# VMEConnectors.net
KiCad netlist of a schematic drawn in Altium Designer
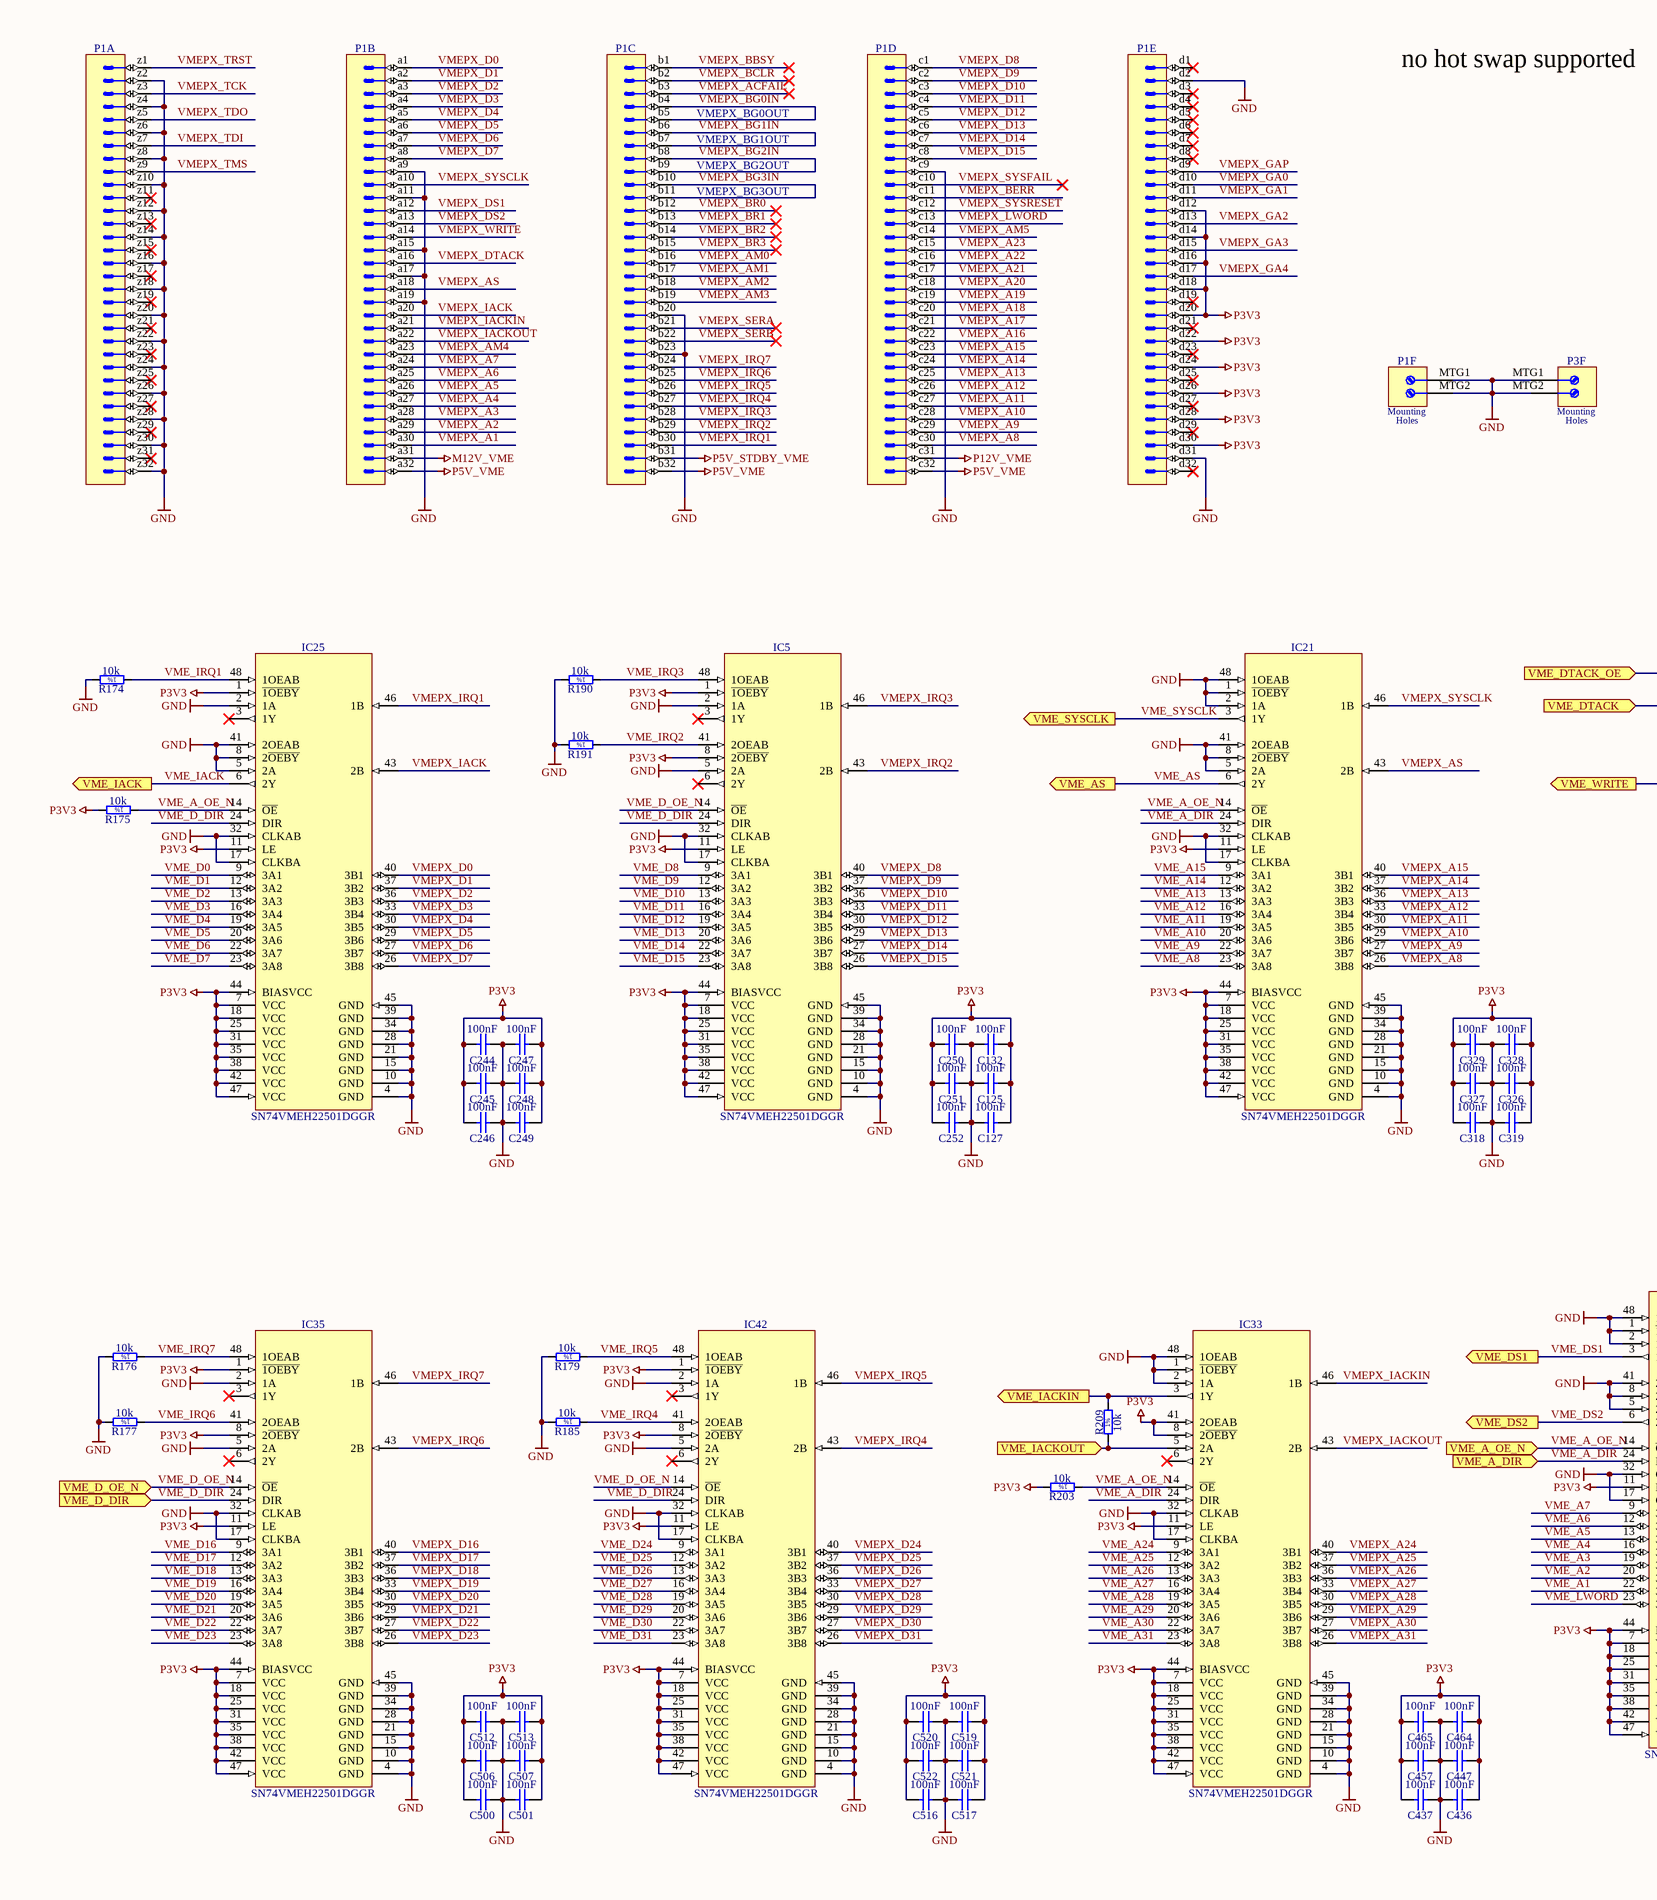
[diagram p0: VMEConnectors.SchDoc, left]
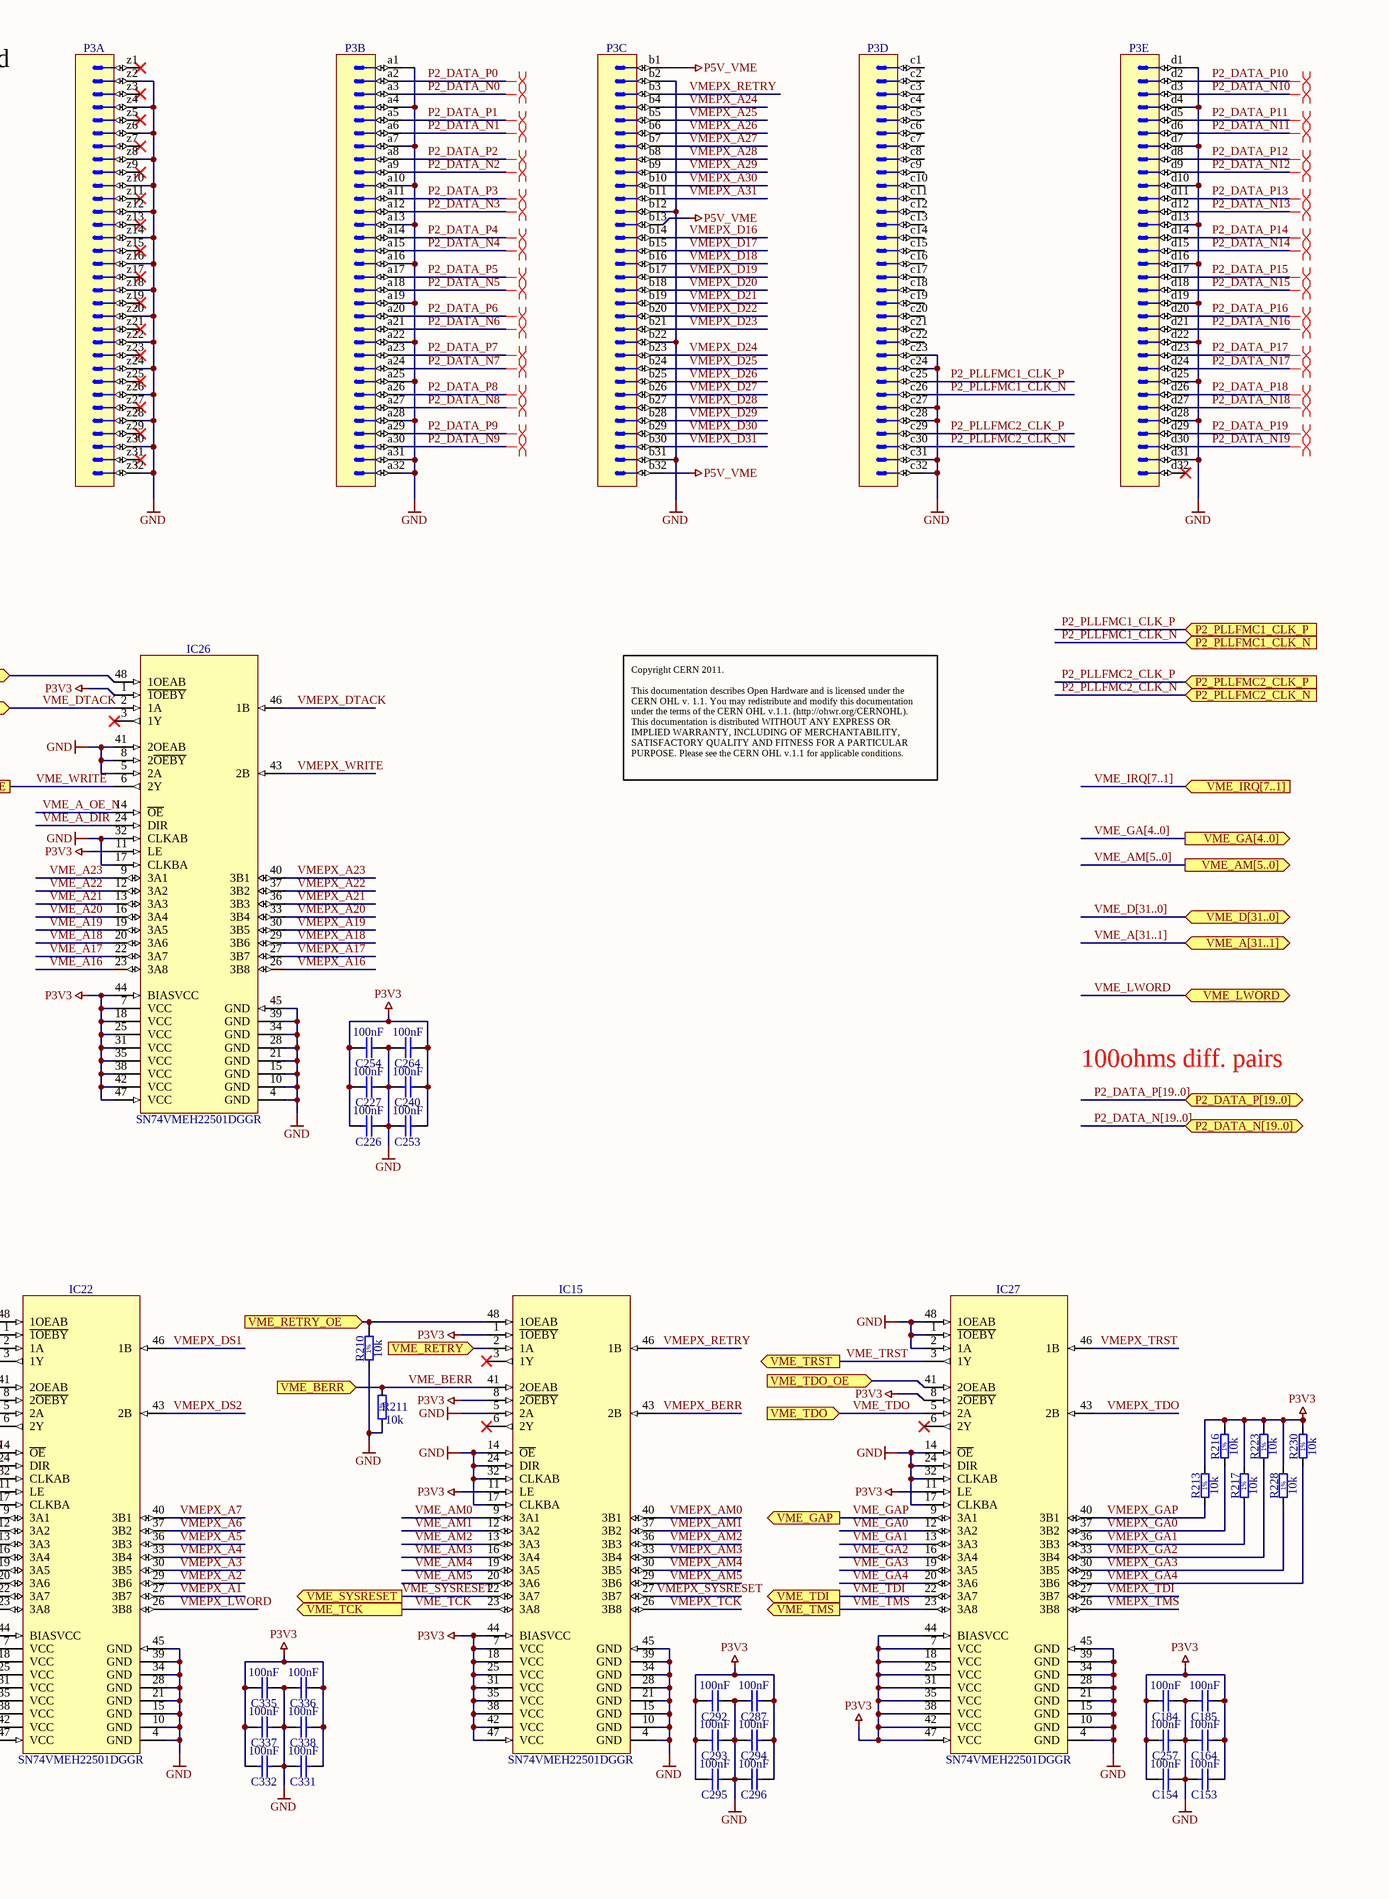
[diagram p1: VMEConnectors.SchDoc, right]

(export (version "E")
  (design (tool "Eeschema 10.0.6"))
  (components
    (comp (ref "C125")
      (value "100nF")
      (footprint "CAPC1005X55N")
      (description "Non-polarised capacitor")
      (fields
        (field (name "PART NUMBER") "CC0402_100NF_16V_10%_X7R")
        (field (name "VOLTAGE") "16V")
        (field (name "AUTHOR") "CERN DEM JLC")
      )
      (libsource (lib "Capacitors") (part "Capacitor - non polarized"))
    )
    (comp (ref "C127")
      (value "100nF")
      (footprint "CAPC1005X55N")
      (description "Non-polarised capacitor")
      (fields
        (field (name "PART NUMBER") "CC0402_100NF_16V_10%_X7R")
        (field (name "VOLTAGE") "16V")
        (field (name "AUTHOR") "CERN DEM JLC")
      )
      (libsource (lib "Capacitors") (part "Capacitor - non polarized"))
    )
    (comp (ref "C132")
      (value "100nF")
      (footprint "CAPC1005X55N")
      (description "Non-polarised capacitor")
      (fields
        (field (name "PART NUMBER") "CC0402_100NF_16V_10%_X7R")
        (field (name "VOLTAGE") "16V")
        (field (name "AUTHOR") "CERN DEM JLC")
      )
      (libsource (lib "Capacitors") (part "Capacitor - non polarized"))
    )
    (comp (ref "C153")
      (value "100nF")
      (footprint "CAPC1005X55N")
      (description "Non-polarised capacitor")
      (fields
        (field (name "PART NUMBER") "CC0402_100NF_16V_10%_X7R")
        (field (name "VOLTAGE") "16V")
        (field (name "AUTHOR") "CERN DEM JLC")
      )
      (libsource (lib "Capacitors") (part "Capacitor - non polarized"))
    )
    (comp (ref "C154")
      (value "100nF")
      (footprint "CAPC1005X55N")
      (description "Non-polarised capacitor")
      (fields
        (field (name "PART NUMBER") "CC0402_100NF_16V_10%_X7R")
        (field (name "VOLTAGE") "16V")
        (field (name "AUTHOR") "CERN DEM JLC")
      )
      (libsource (lib "Capacitors") (part "Capacitor - non polarized"))
    )
    (comp (ref "C164")
      (value "100nF")
      (footprint "CAPC1005X55N")
      (description "Non-polarised capacitor")
      (fields
        (field (name "PART NUMBER") "CC0402_100NF_16V_10%_X7R")
        (field (name "VOLTAGE") "16V")
        (field (name "AUTHOR") "CERN DEM JLC")
      )
      (libsource (lib "Capacitors") (part "Capacitor - non polarized"))
    )
    (comp (ref "C184")
      (value "100nF")
      (footprint "CAPC1005X55N")
      (description "Non-polarised capacitor")
      (fields
        (field (name "PART NUMBER") "CC0402_100NF_16V_10%_X7R")
        (field (name "VOLTAGE") "16V")
        (field (name "AUTHOR") "CERN DEM JLC")
      )
      (libsource (lib "Capacitors") (part "Capacitor - non polarized"))
    )
    (comp (ref "C185")
      (value "100nF")
      (footprint "CAPC1005X55N")
      (description "Non-polarised capacitor")
      (fields
        (field (name "PART NUMBER") "CC0402_100NF_16V_10%_X7R")
        (field (name "VOLTAGE") "16V")
        (field (name "AUTHOR") "CERN DEM JLC")
      )
      (libsource (lib "Capacitors") (part "Capacitor - non polarized"))
    )
    (comp (ref "C226")
      (value "100nF")
      (footprint "CAPC1005X55N")
      (description "Non-polarised capacitor")
      (fields
        (field (name "PART NUMBER") "CC0402_100NF_16V_10%_X7R")
        (field (name "VOLTAGE") "16V")
        (field (name "AUTHOR") "CERN DEM JLC")
      )
      (libsource (lib "Capacitors") (part "Capacitor - non polarized"))
    )
    (comp (ref "C227")
      (value "100nF")
      (footprint "CAPC1005X55N")
      (description "Non-polarised capacitor")
      (fields
        (field (name "PART NUMBER") "CC0402_100NF_16V_10%_X7R")
        (field (name "VOLTAGE") "16V")
        (field (name "AUTHOR") "CERN DEM JLC")
      )
      (libsource (lib "Capacitors") (part "Capacitor - non polarized"))
    )
    (comp (ref "C240")
      (value "100nF")
      (footprint "CAPC1005X55N")
      (description "Non-polarised capacitor")
      (fields
        (field (name "PART NUMBER") "CC0402_100NF_16V_10%_X7R")
        (field (name "VOLTAGE") "16V")
        (field (name "AUTHOR") "CERN DEM JLC")
      )
      (libsource (lib "Capacitors") (part "Capacitor - non polarized"))
    )
    (comp (ref "C244")
      (value "100nF")
      (footprint "CAPC1005X55N")
      (description "Non-polarised capacitor")
      (fields
        (field (name "PART NUMBER") "CC0402_100NF_16V_10%_X7R")
        (field (name "VOLTAGE") "16V")
        (field (name "AUTHOR") "CERN DEM JLC")
      )
      (libsource (lib "Capacitors") (part "Capacitor - non polarized"))
    )
    (comp (ref "C245")
      (value "100nF")
      (footprint "CAPC1005X55N")
      (description "Non-polarised capacitor")
      (fields
        (field (name "PART NUMBER") "CC0402_100NF_16V_10%_X7R")
        (field (name "VOLTAGE") "16V")
        (field (name "AUTHOR") "CERN DEM JLC")
      )
      (libsource (lib "Capacitors") (part "Capacitor - non polarized"))
    )
    (comp (ref "C246")
      (value "100nF")
      (footprint "CAPC1005X55N")
      (description "Non-polarised capacitor")
      (fields
        (field (name "PART NUMBER") "CC0402_100NF_16V_10%_X7R")
        (field (name "VOLTAGE") "16V")
        (field (name "AUTHOR") "CERN DEM JLC")
      )
      (libsource (lib "Capacitors") (part "Capacitor - non polarized"))
    )
    (comp (ref "C247")
      (value "100nF")
      (footprint "CAPC1005X55N")
      (description "Non-polarised capacitor")
      (fields
        (field (name "PART NUMBER") "CC0402_100NF_16V_10%_X7R")
        (field (name "VOLTAGE") "16V")
        (field (name "AUTHOR") "CERN DEM JLC")
      )
      (libsource (lib "Capacitors") (part "Capacitor - non polarized"))
    )
    (comp (ref "C248")
      (value "100nF")
      (footprint "CAPC1005X55N")
      (description "Non-polarised capacitor")
      (fields
        (field (name "PART NUMBER") "CC0402_100NF_16V_10%_X7R")
        (field (name "VOLTAGE") "16V")
        (field (name "AUTHOR") "CERN DEM JLC")
      )
      (libsource (lib "Capacitors") (part "Capacitor - non polarized"))
    )
    (comp (ref "C249")
      (value "100nF")
      (footprint "CAPC1005X55N")
      (description "Non-polarised capacitor")
      (fields
        (field (name "PART NUMBER") "CC0402_100NF_16V_10%_X7R")
        (field (name "VOLTAGE") "16V")
        (field (name "AUTHOR") "CERN DEM JLC")
      )
      (libsource (lib "Capacitors") (part "Capacitor - non polarized"))
    )
    (comp (ref "C250")
      (value "100nF")
      (footprint "CAPC1005X55N")
      (description "Non-polarised capacitor")
      (fields
        (field (name "PART NUMBER") "CC0402_100NF_16V_10%_X7R")
        (field (name "VOLTAGE") "16V")
        (field (name "AUTHOR") "CERN DEM JLC")
      )
      (libsource (lib "Capacitors") (part "Capacitor - non polarized"))
    )
    (comp (ref "C251")
      (value "100nF")
      (footprint "CAPC1005X55N")
      (description "Non-polarised capacitor")
      (fields
        (field (name "PART NUMBER") "CC0402_100NF_16V_10%_X7R")
        (field (name "VOLTAGE") "16V")
        (field (name "AUTHOR") "CERN DEM JLC")
      )
      (libsource (lib "Capacitors") (part "Capacitor - non polarized"))
    )
    (comp (ref "C252")
      (value "100nF")
      (footprint "CAPC1005X55N")
      (description "Non-polarised capacitor")
      (fields
        (field (name "PART NUMBER") "CC0402_100NF_16V_10%_X7R")
        (field (name "VOLTAGE") "16V")
        (field (name "AUTHOR") "CERN DEM JLC")
      )
      (libsource (lib "Capacitors") (part "Capacitor - non polarized"))
    )
    (comp (ref "C253")
      (value "100nF")
      (footprint "CAPC1005X55N")
      (description "Non-polarised capacitor")
      (fields
        (field (name "PART NUMBER") "CC0402_100NF_16V_10%_X7R")
        (field (name "VOLTAGE") "16V")
        (field (name "AUTHOR") "CERN DEM JLC")
      )
      (libsource (lib "Capacitors") (part "Capacitor - non polarized"))
    )
    (comp (ref "C254")
      (value "100nF")
      (footprint "CAPC1005X55N")
      (description "Non-polarised capacitor")
      (fields
        (field (name "PART NUMBER") "CC0402_100NF_16V_10%_X7R")
        (field (name "VOLTAGE") "16V")
        (field (name "AUTHOR") "CERN DEM JLC")
      )
      (libsource (lib "Capacitors") (part "Capacitor - non polarized"))
    )
    (comp (ref "C257")
      (value "100nF")
      (footprint "CAPC1005X55N")
      (description "Non-polarised capacitor")
      (fields
        (field (name "PART NUMBER") "CC0402_100NF_16V_10%_X7R")
        (field (name "VOLTAGE") "16V")
        (field (name "AUTHOR") "CERN DEM JLC")
      )
      (libsource (lib "Capacitors") (part "Capacitor - non polarized"))
    )
    (comp (ref "C264")
      (value "100nF")
      (footprint "CAPC1005X55N")
      (description "Non-polarised capacitor")
      (fields
        (field (name "PART NUMBER") "CC0402_100NF_16V_10%_X7R")
        (field (name "VOLTAGE") "16V")
        (field (name "AUTHOR") "CERN DEM JLC")
      )
      (libsource (lib "Capacitors") (part "Capacitor - non polarized"))
    )
    (comp (ref "C287")
      (value "100nF")
      (footprint "CAPC1005X55N")
      (description "Non-polarised capacitor")
      (fields
        (field (name "PART NUMBER") "CC0402_100NF_16V_10%_X7R")
        (field (name "VOLTAGE") "16V")
        (field (name "AUTHOR") "CERN DEM JLC")
      )
      (libsource (lib "Capacitors") (part "Capacitor - non polarized"))
    )
    (comp (ref "C292")
      (value "100nF")
      (footprint "CAPC1005X55N")
      (description "Non-polarised capacitor")
      (fields
        (field (name "PART NUMBER") "CC0402_100NF_16V_10%_X7R")
        (field (name "VOLTAGE") "16V")
        (field (name "AUTHOR") "CERN DEM JLC")
      )
      (libsource (lib "Capacitors") (part "Capacitor - non polarized"))
    )
    (comp (ref "C293")
      (value "100nF")
      (footprint "CAPC1005X55N")
      (description "Non-polarised capacitor")
      (fields
        (field (name "PART NUMBER") "CC0402_100NF_16V_10%_X7R")
        (field (name "VOLTAGE") "16V")
        (field (name "AUTHOR") "CERN DEM JLC")
      )
      (libsource (lib "Capacitors") (part "Capacitor - non polarized"))
    )
    (comp (ref "C294")
      (value "100nF")
      (footprint "CAPC1005X55N")
      (description "Non-polarised capacitor")
      (fields
        (field (name "PART NUMBER") "CC0402_100NF_16V_10%_X7R")
        (field (name "VOLTAGE") "16V")
        (field (name "AUTHOR") "CERN DEM JLC")
      )
      (libsource (lib "Capacitors") (part "Capacitor - non polarized"))
    )
    (comp (ref "C295")
      (value "100nF")
      (footprint "CAPC1005X55N")
      (description "Non-polarised capacitor")
      (fields
        (field (name "PART NUMBER") "CC0402_100NF_16V_10%_X7R")
        (field (name "VOLTAGE") "16V")
        (field (name "AUTHOR") "CERN DEM JLC")
      )
      (libsource (lib "Capacitors") (part "Capacitor - non polarized"))
    )
    (comp (ref "C296")
      (value "100nF")
      (footprint "CAPC1005X55N")
      (description "Non-polarised capacitor")
      (fields
        (field (name "PART NUMBER") "CC0402_100NF_16V_10%_X7R")
        (field (name "VOLTAGE") "16V")
        (field (name "AUTHOR") "CERN DEM JLC")
      )
      (libsource (lib "Capacitors") (part "Capacitor - non polarized"))
    )
    (comp (ref "C318")
      (value "100nF")
      (footprint "CAPC1005X55N")
      (description "Non-polarised capacitor")
      (fields
        (field (name "PART NUMBER") "CC0402_100NF_16V_10%_X7R")
        (field (name "VOLTAGE") "16V")
        (field (name "AUTHOR") "CERN DEM JLC")
      )
      (libsource (lib "Capacitors") (part "Capacitor - non polarized"))
    )
    (comp (ref "C319")
      (value "100nF")
      (footprint "CAPC1005X55N")
      (description "Non-polarised capacitor")
      (fields
        (field (name "PART NUMBER") "CC0402_100NF_16V_10%_X7R")
        (field (name "VOLTAGE") "16V")
        (field (name "AUTHOR") "CERN DEM JLC")
      )
      (libsource (lib "Capacitors") (part "Capacitor - non polarized"))
    )
    (comp (ref "C326")
      (value "100nF")
      (footprint "CAPC1005X55N")
      (description "Non-polarised capacitor")
      (fields
        (field (name "PART NUMBER") "CC0402_100NF_16V_10%_X7R")
        (field (name "VOLTAGE") "16V")
        (field (name "AUTHOR") "CERN DEM JLC")
      )
      (libsource (lib "Capacitors") (part "Capacitor - non polarized"))
    )
    (comp (ref "C327")
      (value "100nF")
      (footprint "CAPC1005X55N")
      (description "Non-polarised capacitor")
      (fields
        (field (name "PART NUMBER") "CC0402_100NF_16V_10%_X7R")
        (field (name "VOLTAGE") "16V")
        (field (name "AUTHOR") "CERN DEM JLC")
      )
      (libsource (lib "Capacitors") (part "Capacitor - non polarized"))
    )
    (comp (ref "C328")
      (value "100nF")
      (footprint "CAPC1005X55N")
      (description "Non-polarised capacitor")
      (fields
        (field (name "PART NUMBER") "CC0402_100NF_16V_10%_X7R")
        (field (name "VOLTAGE") "16V")
        (field (name "AUTHOR") "CERN DEM JLC")
      )
      (libsource (lib "Capacitors") (part "Capacitor - non polarized"))
    )
    (comp (ref "C329")
      (value "100nF")
      (footprint "CAPC1005X55N")
      (description "Non-polarised capacitor")
      (fields
        (field (name "PART NUMBER") "CC0402_100NF_16V_10%_X7R")
        (field (name "VOLTAGE") "16V")
        (field (name "AUTHOR") "CERN DEM JLC")
      )
      (libsource (lib "Capacitors") (part "Capacitor - non polarized"))
    )
    (comp (ref "C331")
      (value "100nF")
      (footprint "CAPC1005X55N")
      (description "Non-polarised capacitor")
      (fields
        (field (name "PART NUMBER") "CC0402_100NF_16V_10%_X7R")
        (field (name "VOLTAGE") "16V")
        (field (name "AUTHOR") "CERN DEM JLC")
      )
      (libsource (lib "Capacitors") (part "Capacitor - non polarized"))
    )
    (comp (ref "C332")
      (value "100nF")
      (footprint "CAPC1005X55N")
      (description "Non-polarised capacitor")
      (fields
        (field (name "PART NUMBER") "CC0402_100NF_16V_10%_X7R")
        (field (name "VOLTAGE") "16V")
        (field (name "AUTHOR") "CERN DEM JLC")
      )
      (libsource (lib "Capacitors") (part "Capacitor - non polarized"))
    )
    (comp (ref "C335")
      (value "100nF")
      (footprint "CAPC1005X55N")
      (description "Non-polarised capacitor")
      (fields
        (field (name "PART NUMBER") "CC0402_100NF_16V_10%_X7R")
        (field (name "VOLTAGE") "16V")
        (field (name "AUTHOR") "CERN DEM JLC")
      )
      (libsource (lib "Capacitors") (part "Capacitor - non polarized"))
    )
    (comp (ref "C336")
      (value "100nF")
      (footprint "CAPC1005X55N")
      (description "Non-polarised capacitor")
      (fields
        (field (name "PART NUMBER") "CC0402_100NF_16V_10%_X7R")
        (field (name "VOLTAGE") "16V")
        (field (name "AUTHOR") "CERN DEM JLC")
      )
      (libsource (lib "Capacitors") (part "Capacitor - non polarized"))
    )
    (comp (ref "C337")
      (value "100nF")
      (footprint "CAPC1005X55N")
      (description "Non-polarised capacitor")
      (fields
        (field (name "PART NUMBER") "CC0402_100NF_16V_10%_X7R")
        (field (name "VOLTAGE") "16V")
        (field (name "AUTHOR") "CERN DEM JLC")
      )
      (libsource (lib "Capacitors") (part "Capacitor - non polarized"))
    )
    (comp (ref "C338")
      (value "100nF")
      (footprint "CAPC1005X55N")
      (description "Non-polarised capacitor")
      (fields
        (field (name "PART NUMBER") "CC0402_100NF_16V_10%_X7R")
        (field (name "VOLTAGE") "16V")
        (field (name "AUTHOR") "CERN DEM JLC")
      )
      (libsource (lib "Capacitors") (part "Capacitor - non polarized"))
    )
    (comp (ref "C436")
      (value "100nF")
      (footprint "CAPC1005X55N")
      (description "Non-polarised capacitor")
      (fields
        (field (name "PART NUMBER") "CC0402_100NF_16V_10%_X7R")
        (field (name "VOLTAGE") "16V")
        (field (name "AUTHOR") "CERN DEM JLC")
      )
      (libsource (lib "Capacitors") (part "Capacitor - non polarized"))
    )
    (comp (ref "C437")
      (value "100nF")
      (footprint "CAPC1005X55N")
      (description "Non-polarised capacitor")
      (fields
        (field (name "PART NUMBER") "CC0402_100NF_16V_10%_X7R")
        (field (name "VOLTAGE") "16V")
        (field (name "AUTHOR") "CERN DEM JLC")
      )
      (libsource (lib "Capacitors") (part "Capacitor - non polarized"))
    )
    (comp (ref "C447")
      (value "100nF")
      (footprint "CAPC1005X55N")
      (description "Non-polarised capacitor")
      (fields
        (field (name "PART NUMBER") "CC0402_100NF_16V_10%_X7R")
        (field (name "VOLTAGE") "16V")
        (field (name "AUTHOR") "CERN DEM JLC")
      )
      (libsource (lib "Capacitors") (part "Capacitor - non polarized"))
    )
    (comp (ref "C457")
      (value "100nF")
      (footprint "CAPC1005X55N")
      (description "Non-polarised capacitor")
      (fields
        (field (name "PART NUMBER") "CC0402_100NF_16V_10%_X7R")
        (field (name "VOLTAGE") "16V")
        (field (name "AUTHOR") "CERN DEM JLC")
      )
      (libsource (lib "Capacitors") (part "Capacitor - non polarized"))
    )
    (comp (ref "C464")
      (value "100nF")
      (footprint "CAPC1005X55N")
      (description "Non-polarised capacitor")
      (fields
        (field (name "PART NUMBER") "CC0402_100NF_16V_10%_X7R")
        (field (name "VOLTAGE") "16V")
        (field (name "AUTHOR") "CERN DEM JLC")
      )
      (libsource (lib "Capacitors") (part "Capacitor - non polarized"))
    )
    (comp (ref "C465")
      (value "100nF")
      (footprint "CAPC1005X55N")
      (description "Non-polarised capacitor")
      (fields
        (field (name "PART NUMBER") "CC0402_100NF_16V_10%_X7R")
        (field (name "VOLTAGE") "16V")
        (field (name "AUTHOR") "CERN DEM JLC")
      )
      (libsource (lib "Capacitors") (part "Capacitor - non polarized"))
    )
    (comp (ref "C500")
      (value "100nF")
      (footprint "CAPC1005X55N")
      (description "Non-polarised capacitor")
      (fields
        (field (name "PART NUMBER") "CC0402_100NF_16V_10%_X7R")
        (field (name "VOLTAGE") "16V")
        (field (name "AUTHOR") "CERN DEM JLC")
      )
      (libsource (lib "Capacitors") (part "Capacitor - non polarized"))
    )
    (comp (ref "C501")
      (value "100nF")
      (footprint "CAPC1005X55N")
      (description "Non-polarised capacitor")
      (fields
        (field (name "PART NUMBER") "CC0402_100NF_16V_10%_X7R")
        (field (name "VOLTAGE") "16V")
        (field (name "AUTHOR") "CERN DEM JLC")
      )
      (libsource (lib "Capacitors") (part "Capacitor - non polarized"))
    )
    (comp (ref "C506")
      (value "100nF")
      (footprint "CAPC1005X55N")
      (description "Non-polarised capacitor")
      (fields
        (field (name "PART NUMBER") "CC0402_100NF_16V_10%_X7R")
        (field (name "VOLTAGE") "16V")
        (field (name "AUTHOR") "CERN DEM JLC")
      )
      (libsource (lib "Capacitors") (part "Capacitor - non polarized"))
    )
    (comp (ref "C507")
      (value "100nF")
      (footprint "CAPC1005X55N")
      (description "Non-polarised capacitor")
      (fields
        (field (name "PART NUMBER") "CC0402_100NF_16V_10%_X7R")
        (field (name "VOLTAGE") "16V")
        (field (name "AUTHOR") "CERN DEM JLC")
      )
      (libsource (lib "Capacitors") (part "Capacitor - non polarized"))
    )
    (comp (ref "C512")
      (value "100nF")
      (footprint "CAPC1005X55N")
      (description "Non-polarised capacitor")
      (fields
        (field (name "PART NUMBER") "CC0402_100NF_16V_10%_X7R")
        (field (name "VOLTAGE") "16V")
        (field (name "AUTHOR") "CERN DEM JLC")
      )
      (libsource (lib "Capacitors") (part "Capacitor - non polarized"))
    )
    (comp (ref "C513")
      (value "100nF")
      (footprint "CAPC1005X55N")
      (description "Non-polarised capacitor")
      (fields
        (field (name "PART NUMBER") "CC0402_100NF_16V_10%_X7R")
        (field (name "VOLTAGE") "16V")
        (field (name "AUTHOR") "CERN DEM JLC")
      )
      (libsource (lib "Capacitors") (part "Capacitor - non polarized"))
    )
    (comp (ref "C516")
      (value "100nF")
      (footprint "CAPC1005X55N")
      (description "Non-polarised capacitor")
      (fields
        (field (name "PART NUMBER") "CC0402_100NF_16V_10%_X7R")
        (field (name "VOLTAGE") "16V")
        (field (name "AUTHOR") "CERN DEM JLC")
      )
      (libsource (lib "Capacitors") (part "Capacitor - non polarized"))
    )
    (comp (ref "C517")
      (value "100nF")
      (footprint "CAPC1005X55N")
      (description "Non-polarised capacitor")
      (fields
        (field (name "PART NUMBER") "CC0402_100NF_16V_10%_X7R")
        (field (name "VOLTAGE") "16V")
        (field (name "AUTHOR") "CERN DEM JLC")
      )
      (libsource (lib "Capacitors") (part "Capacitor - non polarized"))
    )
    (comp (ref "C519")
      (value "100nF")
      (footprint "CAPC1005X55N")
      (description "Non-polarised capacitor")
      (fields
        (field (name "PART NUMBER") "CC0402_100NF_16V_10%_X7R")
        (field (name "VOLTAGE") "16V")
        (field (name "AUTHOR") "CERN DEM JLC")
      )
      (libsource (lib "Capacitors") (part "Capacitor - non polarized"))
    )
    (comp (ref "C520")
      (value "100nF")
      (footprint "CAPC1005X55N")
      (description "Non-polarised capacitor")
      (fields
        (field (name "PART NUMBER") "CC0402_100NF_16V_10%_X7R")
        (field (name "VOLTAGE") "16V")
        (field (name "AUTHOR") "CERN DEM JLC")
      )
      (libsource (lib "Capacitors") (part "Capacitor - non polarized"))
    )
    (comp (ref "C521")
      (value "100nF")
      (footprint "CAPC1005X55N")
      (description "Non-polarised capacitor")
      (fields
        (field (name "PART NUMBER") "CC0402_100NF_16V_10%_X7R")
        (field (name "VOLTAGE") "16V")
        (field (name "AUTHOR") "CERN DEM JLC")
      )
      (libsource (lib "Capacitors") (part "Capacitor - non polarized"))
    )
    (comp (ref "C522")
      (value "100nF")
      (footprint "CAPC1005X55N")
      (description "Non-polarised capacitor")
      (fields
        (field (name "PART NUMBER") "CC0402_100NF_16V_10%_X7R")
        (field (name "VOLTAGE") "16V")
        (field (name "AUTHOR") "CERN DEM JLC")
      )
      (libsource (lib "Capacitors") (part "Capacitor - non polarized"))
    )
    (comp (ref "IC5")
      (value "SN74VMEH22501DGGR")
      (footprint "SOP50P810X120-48N")
      (description "8-Bit Universal Bus Transceiver and Two 1-Bit Bus Transceivers with 3-State Outputs")
      (fields (field (name "MANUFACTURER") "TEXAS INSTRUMENTS") (field (name "AUTHOR") "CERN DEM JLC"))
      (libsource (lib "ICs And Semiconductors") (part "74VMEH22501"))
    )
    (comp (ref "IC15")
      (value "SN74VMEH22501DGGR")
      (footprint "SOP50P810X120-48N")
      (description "8-Bit Universal Bus Transceiver and Two 1-Bit Bus Transceivers with 3-State Outputs")
      (fields (field (name "MANUFACTURER") "TEXAS INSTRUMENTS") (field (name "AUTHOR") "CERN DEM JLC"))
      (libsource (lib "ICs And Semiconductors") (part "74VMEH22501"))
    )
    (comp (ref "IC21")
      (value "SN74VMEH22501DGGR")
      (footprint "SOP50P810X120-48N")
      (description "8-Bit Universal Bus Transceiver and Two 1-Bit Bus Transceivers with 3-State Outputs")
      (fields (field (name "MANUFACTURER") "TEXAS INSTRUMENTS") (field (name "AUTHOR") "CERN DEM JLC"))
      (libsource (lib "ICs And Semiconductors") (part "74VMEH22501"))
    )
    (comp (ref "IC22")
      (value "SN74VMEH22501DGGR")
      (footprint "SOP50P810X120-48N")
      (description "8-Bit Universal Bus Transceiver and Two 1-Bit Bus Transceivers with 3-State Outputs")
      (fields (field (name "MANUFACTURER") "TEXAS INSTRUMENTS") (field (name "AUTHOR") "CERN DEM JLC"))
      (libsource (lib "ICs And Semiconductors") (part "74VMEH22501"))
    )
    (comp (ref "IC25")
      (value "SN74VMEH22501DGGR")
      (footprint "SOP50P810X120-48N")
      (description "8-Bit Universal Bus Transceiver and Two 1-Bit Bus Transceivers with 3-State Outputs")
      (fields (field (name "MANUFACTURER") "TEXAS INSTRUMENTS") (field (name "AUTHOR") "CERN DEM JLC"))
      (libsource (lib "ICs And Semiconductors") (part "74VMEH22501"))
    )
    (comp (ref "IC26")
      (value "SN74VMEH22501DGGR")
      (footprint "SOP50P810X120-48N")
      (description "8-Bit Universal Bus Transceiver and Two 1-Bit Bus Transceivers with 3-State Outputs")
      (fields (field (name "MANUFACTURER") "TEXAS INSTRUMENTS") (field (name "AUTHOR") "CERN DEM JLC"))
      (libsource (lib "ICs And Semiconductors") (part "74VMEH22501"))
    )
    (comp (ref "IC27")
      (value "SN74VMEH22501DGGR")
      (footprint "SOP50P810X120-48N")
      (description "8-Bit Universal Bus Transceiver and Two 1-Bit Bus Transceivers with 3-State Outputs")
      (fields (field (name "MANUFACTURER") "TEXAS INSTRUMENTS") (field (name "AUTHOR") "CERN DEM JLC"))
      (libsource (lib "ICs And Semiconductors") (part "74VMEH22501"))
    )
    (comp (ref "IC33")
      (value "SN74VMEH22501DGGR")
      (footprint "SOP50P810X120-48N")
      (description "8-Bit Universal Bus Transceiver and Two 1-Bit Bus Transceivers with 3-State Outputs")
      (fields (field (name "MANUFACTURER") "TEXAS INSTRUMENTS") (field (name "AUTHOR") "CERN DEM JLC"))
      (libsource (lib "ICs And Semiconductors") (part "74VMEH22501"))
    )
    (comp (ref "IC35")
      (value "SN74VMEH22501DGGR")
      (footprint "SOP50P810X120-48N")
      (description "8-Bit Universal Bus Transceiver and Two 1-Bit Bus Transceivers with 3-State Outputs")
      (fields (field (name "MANUFACTURER") "TEXAS INSTRUMENTS") (field (name "AUTHOR") "CERN DEM JLC"))
      (libsource (lib "ICs And Semiconductors") (part "74VMEH22501"))
    )
    (comp (ref "IC42")
      (value "SN74VMEH22501DGGR")
      (footprint "SOP50P810X120-48N")
      (description "8-Bit Universal Bus Transceiver and Two 1-Bit Bus Transceivers with 3-State Outputs")
      (fields (field (name "MANUFACTURER") "TEXAS INSTRUMENTS") (field (name "AUTHOR") "CERN DEM JLC"))
      (libsource (lib "ICs And Semiconductors") (part "74VMEH22501"))
    )
    (comp (ref "P1")
      (value "HAR-BUS 64")
      (footprint "HARTING_02 01 160 2101")
      (description "Connector 160zabcd Male (5x32)")
      (fields
        (field (name "PART NUMBER") "HARTING_02 01 160 2101")
        (field (name "MANUFACTURER") "HARTING")
        (field (name "AUTHOR") "CERN DEM JLC")
      )
      (libsource (lib "") (part "Connector 160zabcd Male (5x32)_2"))
    )
    (comp (ref "P3")
      (value "HAR-BUS 64")
      (footprint "HARTING_02 01 160 2101")
      (description "Connector 160zabcd Male (5x32)")
      (fields
        (field (name "PART NUMBER") "HARTING_02 01 160 2101")
        (field (name "MANUFACTURER") "HARTING")
        (field (name "AUTHOR") "CERN DEM JLC")
      )
      (libsource (lib "Connectors") (part "Connector 160zabcd Male (5x32)"))
    )
    (comp (ref "R174")
      (value "10k")
      (footprint "RESC1608X55N")
      (description "Resistor - 1%")
      (fields
        (field (name "PART NUMBER") "R0603_10K_1%_0.1W_100PPM")
        (field (name "POWER") "0.1W")
        (field (name "AUTHOR") "CERN DEM JLC")
      )
      (libsource (lib "Resistors") (part "Resistor - 1%"))
    )
    (comp (ref "R175")
      (value "10k")
      (footprint "RESC1608X55N")
      (description "Resistor - 1%")
      (fields
        (field (name "PART NUMBER") "R0603_10K_1%_0.1W_100PPM")
        (field (name "POWER") "0.1W")
        (field (name "AUTHOR") "CERN DEM JLC")
      )
      (libsource (lib "Resistors") (part "Resistor - 1%"))
    )
    (comp (ref "R176")
      (value "10k")
      (footprint "RESC1608X55N")
      (description "Resistor - 1%")
      (fields
        (field (name "PART NUMBER") "R0603_10K_1%_0.1W_100PPM")
        (field (name "POWER") "0.1W")
        (field (name "AUTHOR") "CERN DEM JLC")
      )
      (libsource (lib "Resistors") (part "Resistor - 1%"))
    )
    (comp (ref "R177")
      (value "10k")
      (footprint "RESC1608X55N")
      (description "Resistor - 1%")
      (fields
        (field (name "PART NUMBER") "R0603_10K_1%_0.1W_100PPM")
        (field (name "POWER") "0.1W")
        (field (name "AUTHOR") "CERN DEM JLC")
      )
      (libsource (lib "Resistors") (part "Resistor - 1%"))
    )
    (comp (ref "R179")
      (value "10k")
      (footprint "RESC1608X55N")
      (description "Resistor - 1%")
      (fields
        (field (name "PART NUMBER") "R0603_10K_1%_0.1W_100PPM")
        (field (name "POWER") "0.1W")
        (field (name "AUTHOR") "CERN DEM JLC")
      )
      (libsource (lib "Resistors") (part "Resistor - 1%"))
    )
    (comp (ref "R185")
      (value "10k")
      (footprint "RESC1608X55N")
      (description "Resistor - 1%")
      (fields
        (field (name "PART NUMBER") "R0603_10K_1%_0.1W_100PPM")
        (field (name "POWER") "0.1W")
        (field (name "AUTHOR") "CERN DEM JLC")
      )
      (libsource (lib "Resistors") (part "Resistor - 1%"))
    )
    (comp (ref "R190")
      (value "10k")
      (footprint "RESC1608X55N")
      (description "Resistor - 1%")
      (fields
        (field (name "PART NUMBER") "R0603_10K_1%_0.1W_100PPM")
        (field (name "POWER") "0.1W")
        (field (name "AUTHOR") "CERN DEM JLC")
      )
      (libsource (lib "Resistors") (part "Resistor - 1%"))
    )
    (comp (ref "R191")
      (value "10k")
      (footprint "RESC1608X55N")
      (description "Resistor - 1%")
      (fields
        (field (name "PART NUMBER") "R0603_10K_1%_0.1W_100PPM")
        (field (name "POWER") "0.1W")
        (field (name "AUTHOR") "CERN DEM JLC")
      )
      (libsource (lib "Resistors") (part "Resistor - 1%"))
    )
    (comp (ref "R203")
      (value "10k")
      (footprint "RESC1608X55N")
      (description "Resistor - 1%")
      (fields
        (field (name "PART NUMBER") "R0603_10K_1%_0.1W_100PPM")
        (field (name "POWER") "0.1W")
        (field (name "AUTHOR") "CERN DEM JLC")
      )
      (libsource (lib "Resistors") (part "Resistor - 1%"))
    )
    (comp (ref "R209")
      (value "10k")
      (footprint "RESC1608X55N")
      (description "Resistor - 1%")
      (fields
        (field (name "PART NUMBER") "R0603_10K_1%_0.1W_100PPM")
        (field (name "POWER") "0.1W")
        (field (name "AUTHOR") "CERN DEM JLC")
      )
      (libsource (lib "Resistors") (part "Resistor - 1%"))
    )
    (comp (ref "R210")
      (value "10k")
      (footprint "RESC1608X55N")
      (description "Resistor - 1%")
      (fields
        (field (name "PART NUMBER") "R0603_10K_1%_0.1W_100PPM")
        (field (name "POWER") "0.1W")
        (field (name "AUTHOR") "CERN DEM JLC")
      )
      (libsource (lib "Resistors") (part "Resistor - 1%"))
    )
    (comp (ref "R211")
      (value "10k")
      (footprint "RESC1608X55N")
      (description "Resistor - 1%")
      (fields
        (field (name "PART NUMBER") "R0603_10K_1%_0.1W_100PPM")
        (field (name "POWER") "0.1W")
        (field (name "AUTHOR") "CERN DEM JLC")
      )
      (libsource (lib "Resistors") (part "Resistor - 1%"))
    )
    (comp (ref "R213")
      (value "10k")
      (footprint "RESC1608X55N")
      (description "Resistor - 1%")
      (fields
        (field (name "PART NUMBER") "R0603_10K_1%_0.1W_100PPM")
        (field (name "POWER") "0.1W")
        (field (name "AUTHOR") "CERN DEM JLC")
      )
      (libsource (lib "Resistors") (part "Resistor - 1%"))
    )
    (comp (ref "R216")
      (value "10k")
      (footprint "RESC1608X55N")
      (description "Resistor - 1%")
      (fields
        (field (name "PART NUMBER") "R0603_10K_1%_0.1W_100PPM")
        (field (name "POWER") "0.1W")
        (field (name "AUTHOR") "CERN DEM JLC")
      )
      (libsource (lib "Resistors") (part "Resistor - 1%"))
    )
    (comp (ref "R217")
      (value "10k")
      (footprint "RESC1608X55N")
      (description "Resistor - 1%")
      (fields
        (field (name "PART NUMBER") "R0603_10K_1%_0.1W_100PPM")
        (field (name "POWER") "0.1W")
        (field (name "AUTHOR") "CERN DEM JLC")
      )
      (libsource (lib "Resistors") (part "Resistor - 1%"))
    )
    (comp (ref "R223")
      (value "10k")
      (footprint "RESC1608X55N")
      (description "Resistor - 1%")
      (fields
        (field (name "PART NUMBER") "R0603_10K_1%_0.1W_100PPM")
        (field (name "POWER") "0.1W")
        (field (name "AUTHOR") "CERN DEM JLC")
      )
      (libsource (lib "Resistors") (part "Resistor - 1%"))
    )
    (comp (ref "R228")
      (value "10k")
      (footprint "RESC1608X55N")
      (description "Resistor - 1%")
      (fields
        (field (name "PART NUMBER") "R0603_10K_1%_0.1W_100PPM")
        (field (name "POWER") "0.1W")
        (field (name "AUTHOR") "CERN DEM JLC")
      )
      (libsource (lib "Resistors") (part "Resistor - 1%"))
    )
    (comp (ref "R230")
      (value "10k")
      (footprint "RESC1608X55N")
      (description "Resistor - 1%")
      (fields
        (field (name "PART NUMBER") "R0603_10K_1%_0.1W_100PPM")
        (field (name "POWER") "0.1W")
        (field (name "AUTHOR") "CERN DEM JLC")
      )
      (libsource (lib "Resistors") (part "Resistor - 1%"))
    )
  )
  (nets
    (net (code "1") (name "/P2_DATA_N0") (class "Default")
      (node (ref "P3") (pin "a3") (pinfunction "a3_a3") (pintype "bidirectional"))
    )
    (net (code "2") (name "/P2_DATA_N1") (class "Default")
      (node (ref "P3") (pin "a6") (pinfunction "a6_a6") (pintype "bidirectional"))
    )
    (net (code "3") (name "/P2_DATA_N2") (class "Default")
      (node (ref "P3") (pin "a9") (pinfunction "a9_a9") (pintype "bidirectional"))
    )
    (net (code "4") (name "/P2_DATA_N3") (class "Default")
      (node (ref "P3") (pin "a12") (pinfunction "a12_a12") (pintype "bidirectional"))
    )
    (net (code "5") (name "/P2_DATA_N4") (class "Default")
      (node (ref "P3") (pin "a15") (pinfunction "a15_a15") (pintype "bidirectional"))
    )
    (net (code "6") (name "/P2_DATA_N5") (class "Default")
      (node (ref "P3") (pin "a18") (pinfunction "a18_a18") (pintype "bidirectional"))
    )
    (net (code "7") (name "/P2_DATA_N6") (class "Default")
      (node (ref "P3") (pin "a21") (pinfunction "a21_a21") (pintype "bidirectional"))
    )
    (net (code "8") (name "/P2_DATA_N7") (class "Default")
      (node (ref "P3") (pin "a24") (pinfunction "a24_a24") (pintype "bidirectional"))
    )
    (net (code "9") (name "/P2_DATA_N8") (class "Default")
      (node (ref "P3") (pin "a27") (pinfunction "a27_a27") (pintype "bidirectional"))
    )
    (net (code "10") (name "/P2_DATA_N9") (class "Default")
      (node (ref "P3") (pin "a30") (pinfunction "a30_a30") (pintype "bidirectional"))
    )
    (net (code "11") (name "/P2_DATA_N10") (class "Default")
      (node (ref "P3") (pin "d3") (pinfunction "d3_d3") (pintype "bidirectional"))
    )
    (net (code "12") (name "/P2_DATA_N11") (class "Default")
      (node (ref "P3") (pin "d6") (pinfunction "d6_d6") (pintype "bidirectional"))
    )
    (net (code "13") (name "/P2_DATA_N12") (class "Default")
      (node (ref "P3") (pin "d9") (pinfunction "d9_d9") (pintype "bidirectional"))
    )
    (net (code "14") (name "/P2_DATA_N13") (class "Default")
      (node (ref "P3") (pin "d12") (pinfunction "d12_d12") (pintype "bidirectional"))
    )
    (net (code "15") (name "/P2_DATA_N14") (class "Default")
      (node (ref "P3") (pin "d15") (pinfunction "d15_d15") (pintype "bidirectional"))
    )
    (net (code "16") (name "/P2_DATA_N15") (class "Default")
      (node (ref "P3") (pin "d18") (pinfunction "d18_d18") (pintype "bidirectional"))
    )
    (net (code "17") (name "/P2_DATA_N16") (class "Default")
      (node (ref "P3") (pin "d21") (pinfunction "d21_d21") (pintype "bidirectional"))
    )
    (net (code "18") (name "/P2_DATA_N17") (class "Default")
      (node (ref "P3") (pin "d24") (pinfunction "d24_d24") (pintype "bidirectional"))
    )
    (net (code "19") (name "/P2_DATA_N18") (class "Default")
      (node (ref "P3") (pin "d27") (pinfunction "d27_d27") (pintype "bidirectional"))
    )
    (net (code "20") (name "/P2_DATA_N19") (class "Default")
      (node (ref "P3") (pin "d30") (pinfunction "d30_d30") (pintype "bidirectional"))
    )
    (net (code "22") (name "/P2_DATA_P0") (class "Default")
      (node (ref "P3") (pin "a2") (pinfunction "a2_a2") (pintype "bidirectional"))
    )
    (net (code "23") (name "/P2_DATA_P1") (class "Default")
      (node (ref "P3") (pin "a5") (pinfunction "a5_a5") (pintype "bidirectional"))
    )
    (net (code "24") (name "/P2_DATA_P2") (class "Default")
      (node (ref "P3") (pin "a8") (pinfunction "a8_a8") (pintype "bidirectional"))
    )
    (net (code "25") (name "/P2_DATA_P3") (class "Default")
      (node (ref "P3") (pin "a11") (pinfunction "a11_a11") (pintype "bidirectional"))
    )
    (net (code "26") (name "/P2_DATA_P4") (class "Default")
      (node (ref "P3") (pin "a14") (pinfunction "a14_a14") (pintype "bidirectional"))
    )
    (net (code "27") (name "/P2_DATA_P5") (class "Default")
      (node (ref "P3") (pin "a17") (pinfunction "a17_a17") (pintype "bidirectional"))
    )
    (net (code "28") (name "/P2_DATA_P6") (class "Default")
      (node (ref "P3") (pin "a20") (pinfunction "a20_a20") (pintype "bidirectional"))
    )
    (net (code "29") (name "/P2_DATA_P7") (class "Default")
      (node (ref "P3") (pin "a23") (pinfunction "a23_a23") (pintype "bidirectional"))
    )
    (net (code "30") (name "/P2_DATA_P8") (class "Default")
      (node (ref "P3") (pin "a26") (pinfunction "a26_a26") (pintype "bidirectional"))
    )
    (net (code "31") (name "/P2_DATA_P9") (class "Default")
      (node (ref "P3") (pin "a29") (pinfunction "a29_a29") (pintype "bidirectional"))
    )
    (net (code "32") (name "/P2_DATA_P10") (class "Default")
      (node (ref "P3") (pin "d2") (pinfunction "d2_d2") (pintype "bidirectional"))
    )
    (net (code "33") (name "/P2_DATA_P11") (class "Default")
      (node (ref "P3") (pin "d5") (pinfunction "d5_d5") (pintype "bidirectional"))
    )
    (net (code "34") (name "/P2_DATA_P12") (class "Default")
      (node (ref "P3") (pin "d8") (pinfunction "d8_d8") (pintype "bidirectional"))
    )
    (net (code "35") (name "/P2_DATA_P13") (class "Default")
      (node (ref "P3") (pin "d11") (pinfunction "d11_d11") (pintype "bidirectional"))
    )
    (net (code "36") (name "/P2_DATA_P14") (class "Default")
      (node (ref "P3") (pin "d14") (pinfunction "d14_d14") (pintype "bidirectional"))
    )
    (net (code "37") (name "/P2_DATA_P15") (class "Default")
      (node (ref "P3") (pin "d17") (pinfunction "d17_d17") (pintype "bidirectional"))
    )
    (net (code "38") (name "/P2_DATA_P16") (class "Default")
      (node (ref "P3") (pin "d20") (pinfunction "d20_d20") (pintype "bidirectional"))
    )
    (net (code "39") (name "/P2_DATA_P17") (class "Default")
      (node (ref "P3") (pin "d23") (pinfunction "d23_d23") (pintype "bidirectional"))
    )
    (net (code "40") (name "/P2_DATA_P18") (class "Default")
      (node (ref "P3") (pin "d26") (pinfunction "d26_d26") (pintype "bidirectional"))
    )
    (net (code "41") (name "/P2_DATA_P19") (class "Default")
      (node (ref "P3") (pin "d29") (pinfunction "d29_d29") (pintype "bidirectional"))
    )
    (net (code "43") (name "/P2_PLLFMC1_CLK_N") (class "Default")
      (node (ref "P3") (pin "c26") (pinfunction "c26_c26") (pintype "bidirectional"))
    )
    (net (code "44") (name "/P2_PLLFMC1_CLK_P") (class "Default")
      (node (ref "P3") (pin "c25") (pinfunction "c25_c25") (pintype "bidirectional"))
    )
    (net (code "45") (name "/P2_PLLFMC2_CLK_N") (class "Default")
      (node (ref "P3") (pin "c30") (pinfunction "c30_c30") (pintype "bidirectional"))
    )
    (net (code "46") (name "/P2_PLLFMC2_CLK_P") (class "Default")
      (node (ref "P3") (pin "c29") (pinfunction "c29_c29") (pintype "bidirectional"))
    )
    (net (code "47") (name "/VMEPX_A1") (class "Default")
      (node (ref "IC22") (pin "27") (pinfunction "3B7_27") (pintype "bidirectional"))
      (node (ref "P1") (pin "a30") (pinfunction "a30_a30") (pintype "bidirectional"))
    )
    (net (code "48") (name "/VMEPX_A2") (class "Default")
      (node (ref "IC22") (pin "29") (pinfunction "3B6_29") (pintype "bidirectional"))
      (node (ref "P1") (pin "a29") (pinfunction "a29_a29") (pintype "bidirectional"))
    )
    (net (code "49") (name "/VMEPX_A3") (class "Default")
      (node (ref "IC22") (pin "30") (pinfunction "3B5_30") (pintype "bidirectional"))
      (node (ref "P1") (pin "a28") (pinfunction "a28_a28") (pintype "bidirectional"))
    )
    (net (code "50") (name "/VMEPX_A4") (class "Default")
      (node (ref "IC22") (pin "33") (pinfunction "3B4_33") (pintype "bidirectional"))
      (node (ref "P1") (pin "a27") (pinfunction "a27_a27") (pintype "bidirectional"))
    )
    (net (code "51") (name "/VMEPX_A5") (class "Default")
      (node (ref "IC22") (pin "36") (pinfunction "3B3_36") (pintype "bidirectional"))
      (node (ref "P1") (pin "a26") (pinfunction "a26_a26") (pintype "bidirectional"))
    )
    (net (code "52") (name "/VMEPX_A6") (class "Default")
      (node (ref "IC22") (pin "37") (pinfunction "3B2_37") (pintype "bidirectional"))
      (node (ref "P1") (pin "a25") (pinfunction "a25_a25") (pintype "bidirectional"))
    )
    (net (code "53") (name "/VMEPX_A7") (class "Default")
      (node (ref "IC22") (pin "40") (pinfunction "3B1_40") (pintype "bidirectional"))
      (node (ref "P1") (pin "a24") (pinfunction "a24_a24") (pintype "bidirectional"))
    )
    (net (code "54") (name "/VMEPX_A8") (class "Default")
      (node (ref "IC21") (pin "26") (pinfunction "3B8_26") (pintype "bidirectional"))
      (node (ref "P1") (pin "c30") (pinfunction "c30_c30") (pintype "bidirectional"))
    )
    (net (code "55") (name "/VMEPX_A9") (class "Default")
      (node (ref "IC21") (pin "27") (pinfunction "3B7_27") (pintype "bidirectional"))
      (node (ref "P1") (pin "c29") (pinfunction "c29_c29") (pintype "bidirectional"))
    )
    (net (code "56") (name "/VMEPX_A10") (class "Default")
      (node (ref "IC21") (pin "29") (pinfunction "3B6_29") (pintype "bidirectional"))
      (node (ref "P1") (pin "c28") (pinfunction "c28_c28") (pintype "bidirectional"))
    )
    (net (code "57") (name "/VMEPX_A11") (class "Default")
      (node (ref "IC21") (pin "30") (pinfunction "3B5_30") (pintype "bidirectional"))
      (node (ref "P1") (pin "c27") (pinfunction "c27_c27") (pintype "bidirectional"))
    )
    (net (code "58") (name "/VMEPX_A12") (class "Default")
      (node (ref "IC21") (pin "33") (pinfunction "3B4_33") (pintype "bidirectional"))
      (node (ref "P1") (pin "c26") (pinfunction "c26_c26") (pintype "bidirectional"))
    )
    (net (code "59") (name "/VMEPX_A13") (class "Default")
      (node (ref "IC21") (pin "36") (pinfunction "3B3_36") (pintype "bidirectional"))
      (node (ref "P1") (pin "c25") (pinfunction "c25_c25") (pintype "bidirectional"))
    )
    (net (code "60") (name "/VMEPX_A14") (class "Default")
      (node (ref "IC21") (pin "37") (pinfunction "3B2_37") (pintype "bidirectional"))
      (node (ref "P1") (pin "c24") (pinfunction "c24_c24") (pintype "bidirectional"))
    )
    (net (code "61") (name "/VMEPX_A15") (class "Default")
      (node (ref "IC21") (pin "40") (pinfunction "3B1_40") (pintype "bidirectional"))
      (node (ref "P1") (pin "c23") (pinfunction "c23_c23") (pintype "bidirectional"))
    )
    (net (code "62") (name "/VMEPX_A16") (class "Default")
      (node (ref "IC26") (pin "26") (pinfunction "3B8_26") (pintype "bidirectional"))
      (node (ref "P1") (pin "c22") (pinfunction "c22_c22") (pintype "bidirectional"))
    )
    (net (code "63") (name "/VMEPX_A17") (class "Default")
      (node (ref "IC26") (pin "27") (pinfunction "3B7_27") (pintype "bidirectional"))
      (node (ref "P1") (pin "c21") (pinfunction "c21_c21") (pintype "bidirectional"))
    )
    (net (code "64") (name "/VMEPX_A18") (class "Default")
      (node (ref "IC26") (pin "29") (pinfunction "3B6_29") (pintype "bidirectional"))
      (node (ref "P1") (pin "c20") (pinfunction "c20_c20") (pintype "bidirectional"))
    )
    (net (code "65") (name "/VMEPX_A19") (class "Default")
      (node (ref "IC26") (pin "30") (pinfunction "3B5_30") (pintype "bidirectional"))
      (node (ref "P1") (pin "c19") (pinfunction "c19_c19") (pintype "bidirectional"))
    )
    (net (code "66") (name "/VMEPX_A20") (class "Default")
      (node (ref "IC26") (pin "33") (pinfunction "3B4_33") (pintype "bidirectional"))
      (node (ref "P1") (pin "c18") (pinfunction "c18_c18") (pintype "bidirectional"))
    )
    (net (code "67") (name "/VMEPX_A21") (class "Default")
      (node (ref "IC26") (pin "36") (pinfunction "3B3_36") (pintype "bidirectional"))
      (node (ref "P1") (pin "c17") (pinfunction "c17_c17") (pintype "bidirectional"))
    )
    (net (code "68") (name "/VMEPX_A22") (class "Default")
      (node (ref "IC26") (pin "37") (pinfunction "3B2_37") (pintype "bidirectional"))
      (node (ref "P1") (pin "c16") (pinfunction "c16_c16") (pintype "bidirectional"))
    )
    (net (code "69") (name "/VMEPX_A23") (class "Default")
      (node (ref "IC26") (pin "40") (pinfunction "3B1_40") (pintype "bidirectional"))
      (node (ref "P1") (pin "c15") (pinfunction "c15_c15") (pintype "bidirectional"))
    )
    (net (code "70") (name "/VMEPX_A24") (class "Default")
      (node (ref "IC33") (pin "40") (pinfunction "3B1_40") (pintype "bidirectional"))
      (node (ref "P3") (pin "b4") (pinfunction "b4_b4") (pintype "bidirectional"))
    )
    (net (code "71") (name "/VMEPX_A25") (class "Default")
      (node (ref "IC33") (pin "37") (pinfunction "3B2_37") (pintype "bidirectional"))
      (node (ref "P3") (pin "b5") (pinfunction "b5_b5") (pintype "bidirectional"))
    )
    (net (code "72") (name "/VMEPX_A26") (class "Default")
      (node (ref "IC33") (pin "36") (pinfunction "3B3_36") (pintype "bidirectional"))
      (node (ref "P3") (pin "b6") (pinfunction "b6_b6") (pintype "bidirectional"))
    )
    (net (code "73") (name "/VMEPX_A27") (class "Default")
      (node (ref "IC33") (pin "33") (pinfunction "3B4_33") (pintype "bidirectional"))
      (node (ref "P3") (pin "b7") (pinfunction "b7_b7") (pintype "bidirectional"))
    )
    (net (code "74") (name "/VMEPX_A28") (class "Default")
      (node (ref "IC33") (pin "30") (pinfunction "3B5_30") (pintype "bidirectional"))
      (node (ref "P3") (pin "b8") (pinfunction "b8_b8") (pintype "bidirectional"))
    )
    (net (code "75") (name "/VMEPX_A29") (class "Default")
      (node (ref "IC33") (pin "29") (pinfunction "3B6_29") (pintype "bidirectional"))
      (node (ref "P3") (pin "b9") (pinfunction "b9_b9") (pintype "bidirectional"))
    )
    (net (code "76") (name "/VMEPX_A30") (class "Default")
      (node (ref "IC33") (pin "27") (pinfunction "3B7_27") (pintype "bidirectional"))
      (node (ref "P3") (pin "b10") (pinfunction "b10_b10") (pintype "bidirectional"))
    )
    (net (code "77") (name "/VMEPX_A31") (class "Default")
      (node (ref "IC33") (pin "26") (pinfunction "3B8_26") (pintype "bidirectional"))
      (node (ref "P3") (pin "b11") (pinfunction "b11_b11") (pintype "bidirectional"))
    )
    (net (code "78") (name "/VMEPX_ACFAIL") (class "Default")
      (node (ref "P1") (pin "b3") (pinfunction "b3_b3") (pintype "bidirectional+no_connect"))
    )
    (net (code "79") (name "/VMEPX_AM0") (class "Default")
      (node (ref "IC15") (pin "40") (pinfunction "3B1_40") (pintype "bidirectional"))
      (node (ref "P1") (pin "b16") (pinfunction "b16_b16") (pintype "bidirectional"))
    )
    (net (code "80") (name "/VMEPX_AM1") (class "Default")
      (node (ref "IC15") (pin "37") (pinfunction "3B2_37") (pintype "bidirectional"))
      (node (ref "P1") (pin "b17") (pinfunction "b17_b17") (pintype "bidirectional"))
    )
    (net (code "81") (name "/VMEPX_AM2") (class "Default")
      (node (ref "IC15") (pin "36") (pinfunction "3B3_36") (pintype "bidirectional"))
      (node (ref "P1") (pin "b18") (pinfunction "b18_b18") (pintype "bidirectional"))
    )
    (net (code "82") (name "/VMEPX_AM3") (class "Default")
      (node (ref "IC15") (pin "33") (pinfunction "3B4_33") (pintype "bidirectional"))
      (node (ref "P1") (pin "b19") (pinfunction "b19_b19") (pintype "bidirectional"))
    )
    (net (code "83") (name "/VMEPX_AM4") (class "Default")
      (node (ref "IC15") (pin "30") (pinfunction "3B5_30") (pintype "bidirectional"))
      (node (ref "P1") (pin "a23") (pinfunction "a23_a23") (pintype "bidirectional"))
    )
    (net (code "84") (name "/VMEPX_AM5") (class "Default")
      (node (ref "IC15") (pin "29") (pinfunction "3B6_29") (pintype "bidirectional"))
      (node (ref "P1") (pin "c14") (pinfunction "c14_c14") (pintype "bidirectional"))
    )
    (net (code "85") (name "/VMEPX_AS") (class "Default")
      (node (ref "IC21") (pin "43") (pinfunction "2B_43") (pintype "input"))
      (node (ref "P1") (pin "a18") (pinfunction "a18_a18") (pintype "bidirectional"))
    )
    (net (code "86") (name "/VMEPX_BBSY") (class "Default")
      (node (ref "P1") (pin "b1") (pinfunction "b1_b1") (pintype "bidirectional+no_connect"))
    )
    (net (code "87") (name "/VMEPX_BCLR") (class "Default")
      (node (ref "P1") (pin "b2") (pinfunction "b2_b2") (pintype "bidirectional+no_connect"))
    )
    (net (code "88") (name "/VMEPX_BERR") (class "Default")
      (node (ref "IC15") (pin "43") (pinfunction "2B_43") (pintype "input"))
      (node (ref "P1") (pin "c11") (pinfunction "c11_c11") (pintype "bidirectional"))
    )
    (net (code "89") (name "/VMEPX_BG0IN") (class "Default")
      (node (ref "P1") (pin "b4") (pinfunction "b4_b4") (pintype "bidirectional"))
      (node (ref "P1") (pin "b5") (pinfunction "b5_b5") (pintype "bidirectional"))
    )
    (net (code "90") (name "/VMEPX_BG1IN") (class "Default")
      (node (ref "P1") (pin "b6") (pinfunction "b6_b6") (pintype "bidirectional"))
      (node (ref "P1") (pin "b7") (pinfunction "b7_b7") (pintype "bidirectional"))
    )
    (net (code "91") (name "/VMEPX_BG2IN") (class "Default")
      (node (ref "P1") (pin "b8") (pinfunction "b8_b8") (pintype "bidirectional"))
      (node (ref "P1") (pin "b9") (pinfunction "b9_b9") (pintype "bidirectional"))
    )
    (net (code "92") (name "/VMEPX_BG3IN") (class "Default")
      (node (ref "P1") (pin "b10") (pinfunction "b10_b10") (pintype "bidirectional"))
      (node (ref "P1") (pin "b11") (pinfunction "b11_b11") (pintype "bidirectional"))
    )
    (net (code "93") (name "/VMEPX_BR0") (class "Default")
      (node (ref "P1") (pin "b12") (pinfunction "b12_b12") (pintype "bidirectional+no_connect"))
    )
    (net (code "94") (name "/VMEPX_BR1") (class "Default")
      (node (ref "P1") (pin "b13") (pinfunction "b13_b13") (pintype "bidirectional+no_connect"))
    )
    (net (code "95") (name "/VMEPX_BR2") (class "Default")
      (node (ref "P1") (pin "b14") (pinfunction "b14_b14") (pintype "bidirectional+no_connect"))
    )
    (net (code "96") (name "/VMEPX_BR3") (class "Default")
      (node (ref "P1") (pin "b15") (pinfunction "b15_b15") (pintype "bidirectional+no_connect"))
    )
    (net (code "97") (name "/VMEPX_D0") (class "Default")
      (node (ref "IC25") (pin "40") (pinfunction "3B1_40") (pintype "bidirectional"))
      (node (ref "P1") (pin "a1") (pinfunction "a1_a1") (pintype "bidirectional"))
    )
    (net (code "98") (name "/VMEPX_D1") (class "Default")
      (node (ref "IC25") (pin "37") (pinfunction "3B2_37") (pintype "bidirectional"))
      (node (ref "P1") (pin "a2") (pinfunction "a2_a2") (pintype "bidirectional"))
    )
    (net (code "99") (name "/VMEPX_D2") (class "Default")
      (node (ref "IC25") (pin "36") (pinfunction "3B3_36") (pintype "bidirectional"))
      (node (ref "P1") (pin "a3") (pinfunction "a3_a3") (pintype "bidirectional"))
    )
    (net (code "100") (name "/VMEPX_D3") (class "Default")
      (node (ref "IC25") (pin "33") (pinfunction "3B4_33") (pintype "bidirectional"))
      (node (ref "P1") (pin "a4") (pinfunction "a4_a4") (pintype "bidirectional"))
    )
    (net (code "101") (name "/VMEPX_D4") (class "Default")
      (node (ref "IC25") (pin "30") (pinfunction "3B5_30") (pintype "bidirectional"))
      (node (ref "P1") (pin "a5") (pinfunction "a5_a5") (pintype "bidirectional"))
    )
    (net (code "102") (name "/VMEPX_D5") (class "Default")
      (node (ref "IC25") (pin "29") (pinfunction "3B6_29") (pintype "bidirectional"))
      (node (ref "P1") (pin "a6") (pinfunction "a6_a6") (pintype "bidirectional"))
    )
    (net (code "103") (name "/VMEPX_D6") (class "Default")
      (node (ref "IC25") (pin "27") (pinfunction "3B7_27") (pintype "bidirectional"))
      (node (ref "P1") (pin "a7") (pinfunction "a7_a7") (pintype "bidirectional"))
    )
    (net (code "104") (name "/VMEPX_D7") (class "Default")
      (node (ref "IC25") (pin "26") (pinfunction "3B8_26") (pintype "bidirectional"))
      (node (ref "P1") (pin "a8") (pinfunction "a8_a8") (pintype "bidirectional"))
    )
    (net (code "105") (name "/VMEPX_D8") (class "Default")
      (node (ref "IC5") (pin "40") (pinfunction "3B1_40") (pintype "bidirectional"))
      (node (ref "P1") (pin "c1") (pinfunction "c1_c1") (pintype "bidirectional"))
    )
    (net (code "106") (name "/VMEPX_D9") (class "Default")
      (node (ref "IC5") (pin "37") (pinfunction "3B2_37") (pintype "bidirectional"))
      (node (ref "P1") (pin "c2") (pinfunction "c2_c2") (pintype "bidirectional"))
    )
    (net (code "107") (name "/VMEPX_D10") (class "Default")
      (node (ref "IC5") (pin "36") (pinfunction "3B3_36") (pintype "bidirectional"))
      (node (ref "P1") (pin "c3") (pinfunction "c3_c3") (pintype "bidirectional"))
    )
    (net (code "108") (name "/VMEPX_D11") (class "Default")
      (node (ref "IC5") (pin "33") (pinfunction "3B4_33") (pintype "bidirectional"))
      (node (ref "P1") (pin "c4") (pinfunction "c4_c4") (pintype "bidirectional"))
    )
    (net (code "109") (name "/VMEPX_D12") (class "Default")
      (node (ref "IC5") (pin "30") (pinfunction "3B5_30") (pintype "bidirectional"))
      (node (ref "P1") (pin "c5") (pinfunction "c5_c5") (pintype "bidirectional"))
    )
    (net (code "110") (name "/VMEPX_D13") (class "Default")
      (node (ref "IC5") (pin "29") (pinfunction "3B6_29") (pintype "bidirectional"))
      (node (ref "P1") (pin "c6") (pinfunction "c6_c6") (pintype "bidirectional"))
    )
    (net (code "111") (name "/VMEPX_D14") (class "Default")
      (node (ref "IC5") (pin "27") (pinfunction "3B7_27") (pintype "bidirectional"))
      (node (ref "P1") (pin "c7") (pinfunction "c7_c7") (pintype "bidirectional"))
    )
    (net (code "112") (name "/VMEPX_D15") (class "Default")
      (node (ref "IC5") (pin "26") (pinfunction "3B8_26") (pintype "bidirectional"))
      (node (ref "P1") (pin "c8") (pinfunction "c8_c8") (pintype "bidirectional"))
    )
    (net (code "113") (name "/VMEPX_D16") (class "Default")
      (node (ref "IC35") (pin "40") (pinfunction "3B1_40") (pintype "bidirectional"))
      (node (ref "P3") (pin "b14") (pinfunction "b14_b14") (pintype "bidirectional"))
    )
    (net (code "114") (name "/VMEPX_D17") (class "Default")
      (node (ref "IC35") (pin "37") (pinfunction "3B2_37") (pintype "bidirectional"))
      (node (ref "P3") (pin "b15") (pinfunction "b15_b15") (pintype "bidirectional"))
    )
    (net (code "115") (name "/VMEPX_D18") (class "Default")
      (node (ref "IC35") (pin "36") (pinfunction "3B3_36") (pintype "bidirectional"))
      (node (ref "P3") (pin "b16") (pinfunction "b16_b16") (pintype "bidirectional"))
    )
    (net (code "116") (name "/VMEPX_D19") (class "Default")
      (node (ref "IC35") (pin "33") (pinfunction "3B4_33") (pintype "bidirectional"))
      (node (ref "P3") (pin "b17") (pinfunction "b17_b17") (pintype "bidirectional"))
    )
    (net (code "117") (name "/VMEPX_D20") (class "Default")
      (node (ref "IC35") (pin "30") (pinfunction "3B5_30") (pintype "bidirectional"))
      (node (ref "P3") (pin "b18") (pinfunction "b18_b18") (pintype "bidirectional"))
    )
    (net (code "118") (name "/VMEPX_D21") (class "Default")
      (node (ref "IC35") (pin "29") (pinfunction "3B6_29") (pintype "bidirectional"))
      (node (ref "P3") (pin "b19") (pinfunction "b19_b19") (pintype "bidirectional"))
    )
    (net (code "119") (name "/VMEPX_D22") (class "Default")
      (node (ref "IC35") (pin "27") (pinfunction "3B7_27") (pintype "bidirectional"))
      (node (ref "P3") (pin "b20") (pinfunction "b20_b20") (pintype "bidirectional"))
    )
    (net (code "120") (name "/VMEPX_D23") (class "Default")
      (node (ref "IC35") (pin "26") (pinfunction "3B8_26") (pintype "bidirectional"))
      (node (ref "P3") (pin "b21") (pinfunction "b21_b21") (pintype "bidirectional"))
    )
    (net (code "121") (name "/VMEPX_D24") (class "Default")
      (node (ref "IC42") (pin "40") (pinfunction "3B1_40") (pintype "bidirectional"))
      (node (ref "P3") (pin "b23") (pinfunction "b23_b23") (pintype "bidirectional"))
    )
    (net (code "122") (name "/VMEPX_D25") (class "Default")
      (node (ref "IC42") (pin "37") (pinfunction "3B2_37") (pintype "bidirectional"))
      (node (ref "P3") (pin "b24") (pinfunction "b24_b24") (pintype "bidirectional"))
    )
    (net (code "123") (name "/VMEPX_D26") (class "Default")
      (node (ref "IC42") (pin "36") (pinfunction "3B3_36") (pintype "bidirectional"))
      (node (ref "P3") (pin "b25") (pinfunction "b25_b25") (pintype "bidirectional"))
    )
    (net (code "124") (name "/VMEPX_D27") (class "Default")
      (node (ref "IC42") (pin "33") (pinfunction "3B4_33") (pintype "bidirectional"))
      (node (ref "P3") (pin "b26") (pinfunction "b26_b26") (pintype "bidirectional"))
    )
    (net (code "125") (name "/VMEPX_D28") (class "Default")
      (node (ref "IC42") (pin "30") (pinfunction "3B5_30") (pintype "bidirectional"))
      (node (ref "P3") (pin "b27") (pinfunction "b27_b27") (pintype "bidirectional"))
    )
    (net (code "126") (name "/VMEPX_D29") (class "Default")
      (node (ref "IC42") (pin "29") (pinfunction "3B6_29") (pintype "bidirectional"))
      (node (ref "P3") (pin "b28") (pinfunction "b28_b28") (pintype "bidirectional"))
    )
    (net (code "127") (name "/VMEPX_D30") (class "Default")
      (node (ref "IC42") (pin "27") (pinfunction "3B7_27") (pintype "bidirectional"))
      (node (ref "P3") (pin "b29") (pinfunction "b29_b29") (pintype "bidirectional"))
    )
    (net (code "128") (name "/VMEPX_D31") (class "Default")
      (node (ref "IC42") (pin "26") (pinfunction "3B8_26") (pintype "bidirectional"))
      (node (ref "P3") (pin "b30") (pinfunction "b30_b30") (pintype "bidirectional"))
    )
    (net (code "129") (name "/VMEPX_DS1") (class "Default")
      (node (ref "IC22") (pin "46") (pinfunction "1B_46") (pintype "input"))
      (node (ref "P1") (pin "a12") (pinfunction "a12_a12") (pintype "bidirectional"))
    )
    (net (code "130") (name "/VMEPX_DS2") (class "Default")
      (node (ref "IC22") (pin "43") (pinfunction "2B_43") (pintype "input"))
      (node (ref "P1") (pin "a13") (pinfunction "a13_a13") (pintype "bidirectional"))
    )
    (net (code "131") (name "/VMEPX_DTACK") (class "Default")
      (node (ref "IC26") (pin "46") (pinfunction "1B_46") (pintype "input"))
      (node (ref "P1") (pin "a16") (pinfunction "a16_a16") (pintype "bidirectional"))
    )
    (net (code "132") (name "/VMEPX_GA0") (class "Default")
      (node (ref "IC27") (pin "37") (pinfunction "3B2_37") (pintype "bidirectional"))
      (node (ref "P1") (pin "d10") (pinfunction "d10_d10") (pintype "bidirectional"))
      (node (ref "R216") (pin "1") (pinfunction "1_1") (pintype "passive"))
    )
    (net (code "133") (name "/VMEPX_GA1") (class "Default")
      (node (ref "IC27") (pin "36") (pinfunction "3B3_36") (pintype "bidirectional"))
      (node (ref "P1") (pin "d11") (pinfunction "d11_d11") (pintype "bidirectional"))
      (node (ref "R217") (pin "1") (pinfunction "1_1") (pintype "passive"))
    )
    (net (code "134") (name "/VMEPX_GA2") (class "Default")
      (node (ref "IC27") (pin "33") (pinfunction "3B4_33") (pintype "bidirectional"))
      (node (ref "P1") (pin "d13") (pinfunction "d13_d13") (pintype "bidirectional"))
      (node (ref "R223") (pin "1") (pinfunction "1_1") (pintype "passive"))
    )
    (net (code "135") (name "/VMEPX_GA3") (class "Default")
      (node (ref "IC27") (pin "30") (pinfunction "3B5_30") (pintype "bidirectional"))
      (node (ref "P1") (pin "d15") (pinfunction "d15_d15") (pintype "bidirectional"))
      (node (ref "R228") (pin "1") (pinfunction "1_1") (pintype "passive"))
    )
    (net (code "136") (name "/VMEPX_GA4") (class "Default")
      (node (ref "IC27") (pin "29") (pinfunction "3B6_29") (pintype "bidirectional"))
      (node (ref "P1") (pin "d17") (pinfunction "d17_d17") (pintype "bidirectional"))
      (node (ref "R230") (pin "1") (pinfunction "1_1") (pintype "passive"))
    )
    (net (code "137") (name "/VMEPX_GAP") (class "Default")
      (node (ref "IC27") (pin "40") (pinfunction "3B1_40") (pintype "bidirectional"))
      (node (ref "P1") (pin "d9") (pinfunction "d9_d9") (pintype "bidirectional"))
      (node (ref "R213") (pin "1") (pinfunction "1_1") (pintype "passive"))
    )
    (net (code "138") (name "/VMEPX_IACK") (class "Default")
      (node (ref "IC25") (pin "43") (pinfunction "2B_43") (pintype "input"))
      (node (ref "P1") (pin "a20") (pinfunction "a20_a20") (pintype "bidirectional"))
    )
    (net (code "139") (name "/VMEPX_IACKIN") (class "Default")
      (node (ref "IC33") (pin "46") (pinfunction "1B_46") (pintype "input"))
      (node (ref "P1") (pin "a21") (pinfunction "a21_a21") (pintype "bidirectional"))
    )
    (net (code "140") (name "/VMEPX_IACKOUT") (class "Default")
      (node (ref "IC33") (pin "43") (pinfunction "2B_43") (pintype "input"))
      (node (ref "P1") (pin "a22") (pinfunction "a22_a22") (pintype "bidirectional"))
    )
    (net (code "141") (name "/VMEPX_IRQ1") (class "Default")
      (node (ref "IC25") (pin "46") (pinfunction "1B_46") (pintype "input"))
      (node (ref "P1") (pin "b30") (pinfunction "b30_b30") (pintype "bidirectional"))
    )
    (net (code "142") (name "/VMEPX_IRQ2") (class "Default")
      (node (ref "IC5") (pin "43") (pinfunction "2B_43") (pintype "input"))
      (node (ref "P1") (pin "b29") (pinfunction "b29_b29") (pintype "bidirectional"))
    )
    (net (code "143") (name "/VMEPX_IRQ3") (class "Default")
      (node (ref "IC5") (pin "46") (pinfunction "1B_46") (pintype "input"))
      (node (ref "P1") (pin "b28") (pinfunction "b28_b28") (pintype "bidirectional"))
    )
    (net (code "144") (name "/VMEPX_IRQ4") (class "Default")
      (node (ref "IC42") (pin "43") (pinfunction "2B_43") (pintype "input"))
      (node (ref "P1") (pin "b27") (pinfunction "b27_b27") (pintype "bidirectional"))
    )
    (net (code "145") (name "/VMEPX_IRQ5") (class "Default")
      (node (ref "IC42") (pin "46") (pinfunction "1B_46") (pintype "input"))
      (node (ref "P1") (pin "b26") (pinfunction "b26_b26") (pintype "bidirectional"))
    )
    (net (code "146") (name "/VMEPX_IRQ6") (class "Default")
      (node (ref "IC35") (pin "43") (pinfunction "2B_43") (pintype "input"))
      (node (ref "P1") (pin "b25") (pinfunction "b25_b25") (pintype "bidirectional"))
    )
    (net (code "147") (name "/VMEPX_IRQ7") (class "Default")
      (node (ref "IC35") (pin "46") (pinfunction "1B_46") (pintype "input"))
      (node (ref "P1") (pin "b24") (pinfunction "b24_b24") (pintype "bidirectional"))
    )
    (net (code "148") (name "/VMEPX_LWORD") (class "Default")
      (node (ref "IC22") (pin "26") (pinfunction "3B8_26") (pintype "bidirectional"))
      (node (ref "P1") (pin "c13") (pinfunction "c13_c13") (pintype "bidirectional"))
    )
    (net (code "149") (name "/VMEPX_RETRY") (class "Default")
      (node (ref "IC15") (pin "46") (pinfunction "1B_46") (pintype "input"))
      (node (ref "P3") (pin "b3") (pinfunction "b3_b3") (pintype "bidirectional"))
    )
    (net (code "150") (name "/VMEPX_SERA") (class "Default")
      (node (ref "P1") (pin "b21") (pinfunction "b21_b21") (pintype "bidirectional+no_connect"))
    )
    (net (code "151") (name "/VMEPX_SERB") (class "Default")
      (node (ref "P1") (pin "b22") (pinfunction "b22_b22") (pintype "bidirectional+no_connect"))
    )
    (net (code "152") (name "/VMEPX_SYSCLK") (class "Default")
      (node (ref "IC21") (pin "46") (pinfunction "1B_46") (pintype "input"))
      (node (ref "P1") (pin "a10") (pinfunction "a10_a10") (pintype "bidirectional"))
    )
    (net (code "153") (name "/VMEPX_SYSFAIL") (class "Default")
      (node (ref "P1") (pin "c10") (pinfunction "c10_c10") (pintype "bidirectional+no_connect"))
    )
    (net (code "154") (name "/VMEPX_SYSRESET") (class "Default")
      (node (ref "IC15") (pin "27") (pinfunction "3B7_27") (pintype "bidirectional"))
      (node (ref "P1") (pin "c12") (pinfunction "c12_c12") (pintype "bidirectional"))
    )
    (net (code "155") (name "/VMEPX_TCK") (class "Default")
      (node (ref "IC15") (pin "26") (pinfunction "3B8_26") (pintype "bidirectional"))
      (node (ref "P1") (pin "z3") (pinfunction "z3_z3") (pintype "bidirectional"))
    )
    (net (code "156") (name "/VMEPX_TDI") (class "Default")
      (node (ref "IC27") (pin "27") (pinfunction "3B7_27") (pintype "bidirectional"))
      (node (ref "P1") (pin "z7") (pinfunction "z7_z7") (pintype "bidirectional"))
    )
    (net (code "157") (name "/VMEPX_TDO") (class "Default")
      (node (ref "IC27") (pin "43") (pinfunction "2B_43") (pintype "input"))
      (node (ref "P1") (pin "z5") (pinfunction "z5_z5") (pintype "bidirectional"))
    )
    (net (code "158") (name "/VMEPX_TMS") (class "Default")
      (node (ref "IC27") (pin "26") (pinfunction "3B8_26") (pintype "bidirectional"))
      (node (ref "P1") (pin "z9") (pinfunction "z9_z9") (pintype "bidirectional"))
    )
    (net (code "159") (name "/VMEPX_TRST") (class "Default")
      (node (ref "IC27") (pin "46") (pinfunction "1B_46") (pintype "input"))
      (node (ref "P1") (pin "z1") (pinfunction "z1_z1") (pintype "bidirectional"))
    )
    (net (code "160") (name "/VMEPX_WRITE") (class "Default")
      (node (ref "IC26") (pin "43") (pinfunction "2B_43") (pintype "input"))
      (node (ref "P1") (pin "a14") (pinfunction "a14_a14") (pintype "bidirectional"))
    )
    (net (code "161") (name "/VME_A1") (class "Default")
      (node (ref "IC22") (pin "22") (pinfunction "3A7_22") (pintype "bidirectional"))
    )
    (net (code "162") (name "/VME_A2") (class "Default")
      (node (ref "IC22") (pin "20") (pinfunction "3A6_20") (pintype "bidirectional"))
    )
    (net (code "163") (name "/VME_A3") (class "Default")
      (node (ref "IC22") (pin "19") (pinfunction "3A5_19") (pintype "bidirectional"))
    )
    (net (code "164") (name "/VME_A4") (class "Default")
      (node (ref "IC22") (pin "16") (pinfunction "3A4_16") (pintype "bidirectional"))
    )
    (net (code "165") (name "/VME_A5") (class "Default")
      (node (ref "IC22") (pin "13") (pinfunction "3A3_13") (pintype "bidirectional"))
    )
    (net (code "166") (name "/VME_A6") (class "Default")
      (node (ref "IC22") (pin "12") (pinfunction "3A2_12") (pintype "bidirectional"))
    )
    (net (code "167") (name "/VME_A7") (class "Default")
      (node (ref "IC22") (pin "9") (pinfunction "3A1_9") (pintype "bidirectional"))
    )
    (net (code "168") (name "/VME_A8") (class "Default")
      (node (ref "IC21") (pin "23") (pinfunction "3A8_23") (pintype "bidirectional"))
    )
    (net (code "169") (name "/VME_A9") (class "Default")
      (node (ref "IC21") (pin "22") (pinfunction "3A7_22") (pintype "bidirectional"))
    )
    (net (code "170") (name "/VME_A10") (class "Default")
      (node (ref "IC21") (pin "20") (pinfunction "3A6_20") (pintype "bidirectional"))
    )
    (net (code "171") (name "/VME_A11") (class "Default")
      (node (ref "IC21") (pin "19") (pinfunction "3A5_19") (pintype "bidirectional"))
    )
    (net (code "172") (name "/VME_A12") (class "Default")
      (node (ref "IC21") (pin "16") (pinfunction "3A4_16") (pintype "bidirectional"))
    )
    (net (code "173") (name "/VME_A13") (class "Default")
      (node (ref "IC21") (pin "13") (pinfunction "3A3_13") (pintype "bidirectional"))
    )
    (net (code "174") (name "/VME_A14") (class "Default")
      (node (ref "IC21") (pin "12") (pinfunction "3A2_12") (pintype "bidirectional"))
    )
    (net (code "175") (name "/VME_A15") (class "Default")
      (node (ref "IC21") (pin "9") (pinfunction "3A1_9") (pintype "bidirectional"))
    )
    (net (code "176") (name "/VME_A16") (class "Default")
      (node (ref "IC26") (pin "23") (pinfunction "3A8_23") (pintype "bidirectional"))
    )
    (net (code "177") (name "/VME_A17") (class "Default")
      (node (ref "IC26") (pin "22") (pinfunction "3A7_22") (pintype "bidirectional"))
    )
    (net (code "178") (name "/VME_A18") (class "Default")
      (node (ref "IC26") (pin "20") (pinfunction "3A6_20") (pintype "bidirectional"))
    )
    (net (code "179") (name "/VME_A19") (class "Default")
      (node (ref "IC26") (pin "19") (pinfunction "3A5_19") (pintype "bidirectional"))
    )
    (net (code "180") (name "/VME_A20") (class "Default")
      (node (ref "IC26") (pin "16") (pinfunction "3A4_16") (pintype "bidirectional"))
    )
    (net (code "181") (name "/VME_A21") (class "Default")
      (node (ref "IC26") (pin "13") (pinfunction "3A3_13") (pintype "bidirectional"))
    )
    (net (code "182") (name "/VME_A22") (class "Default")
      (node (ref "IC26") (pin "12") (pinfunction "3A2_12") (pintype "bidirectional"))
    )
    (net (code "183") (name "/VME_A23") (class "Default")
      (node (ref "IC26") (pin "9") (pinfunction "3A1_9") (pintype "bidirectional"))
    )
    (net (code "184") (name "/VME_A24") (class "Default")
      (node (ref "IC33") (pin "9") (pinfunction "3A1_9") (pintype "bidirectional"))
    )
    (net (code "185") (name "/VME_A25") (class "Default")
      (node (ref "IC33") (pin "12") (pinfunction "3A2_12") (pintype "bidirectional"))
    )
    (net (code "186") (name "/VME_A26") (class "Default")
      (node (ref "IC33") (pin "13") (pinfunction "3A3_13") (pintype "bidirectional"))
    )
    (net (code "187") (name "/VME_A27") (class "Default")
      (node (ref "IC33") (pin "16") (pinfunction "3A4_16") (pintype "bidirectional"))
    )
    (net (code "188") (name "/VME_A28") (class "Default")
      (node (ref "IC33") (pin "19") (pinfunction "3A5_19") (pintype "bidirectional"))
    )
    (net (code "189") (name "/VME_A29") (class "Default")
      (node (ref "IC33") (pin "20") (pinfunction "3A6_20") (pintype "bidirectional"))
    )
    (net (code "190") (name "/VME_A30") (class "Default")
      (node (ref "IC33") (pin "22") (pinfunction "3A7_22") (pintype "bidirectional"))
    )
    (net (code "191") (name "/VME_A31") (class "Default")
      (node (ref "IC33") (pin "23") (pinfunction "3A8_23") (pintype "bidirectional"))
    )
    (net (code "192") (name "/VME_AM0") (class "Default")
      (node (ref "IC15") (pin "9") (pinfunction "3A1_9") (pintype "bidirectional"))
    )
    (net (code "193") (name "/VME_AM1") (class "Default")
      (node (ref "IC15") (pin "12") (pinfunction "3A2_12") (pintype "bidirectional"))
    )
    (net (code "194") (name "/VME_AM2") (class "Default")
      (node (ref "IC15") (pin "13") (pinfunction "3A3_13") (pintype "bidirectional"))
    )
    (net (code "195") (name "/VME_AM3") (class "Default")
      (node (ref "IC15") (pin "16") (pinfunction "3A4_16") (pintype "bidirectional"))
    )
    (net (code "196") (name "/VME_AM4") (class "Default")
      (node (ref "IC15") (pin "19") (pinfunction "3A5_19") (pintype "bidirectional"))
    )
    (net (code "197") (name "/VME_AM5") (class "Default")
      (node (ref "IC15") (pin "20") (pinfunction "3A6_20") (pintype "bidirectional"))
    )
    (net (code "199") (name "/VME_AS") (class "Default")
      (node (ref "IC21") (pin "6") (pinfunction "2Y_6") (pintype "output"))
    )
    (net (code "201") (name "/VME_A_DIR") (class "Default")
      (node (ref "IC21") (pin "24") (pinfunction "DIR_24") (pintype "input"))
      (node (ref "IC22") (pin "24") (pinfunction "DIR_24") (pintype "input"))
      (node (ref "IC26") (pin "24") (pinfunction "DIR_24") (pintype "input"))
      (node (ref "IC33") (pin "24") (pinfunction "DIR_24") (pintype "input"))
    )
    (net (code "202") (name "/VME_A_OE_N") (class "Default")
      (node (ref "IC21") (pin "14") (pinfunction "~{OE}_14") (pintype "input"))
      (node (ref "IC22") (pin "14") (pinfunction "~{OE}_14") (pintype "input"))
      (node (ref "IC25") (pin "14") (pinfunction "~{OE}_14") (pintype "input"))
      (node (ref "IC26") (pin "14") (pinfunction "~{OE}_14") (pintype "input"))
      (node (ref "IC33") (pin "14") (pinfunction "~{OE}_14") (pintype "input"))
      (node (ref "R175") (pin "1") (pinfunction "1_1") (pintype "passive"))
      (node (ref "R203") (pin "1") (pinfunction "1_1") (pintype "passive"))
    )
    (net (code "203") (name "/VME_BERR") (class "Default")
      (node (ref "IC15") (pin "41") (pinfunction "2OEAB_41") (pintype "input"))
      (node (ref "R211") (pin "2") (pinfunction "2_2") (pintype "passive"))
    )
    (net (code "204") (name "/VME_D0") (class "Default")
      (node (ref "IC25") (pin "9") (pinfunction "3A1_9") (pintype "bidirectional"))
    )
    (net (code "205") (name "/VME_D1") (class "Default")
      (node (ref "IC25") (pin "12") (pinfunction "3A2_12") (pintype "bidirectional"))
    )
    (net (code "206") (name "/VME_D2") (class "Default")
      (node (ref "IC25") (pin "13") (pinfunction "3A3_13") (pintype "bidirectional"))
    )
    (net (code "207") (name "/VME_D3") (class "Default")
      (node (ref "IC25") (pin "16") (pinfunction "3A4_16") (pintype "bidirectional"))
    )
    (net (code "208") (name "/VME_D4") (class "Default")
      (node (ref "IC25") (pin "19") (pinfunction "3A5_19") (pintype "bidirectional"))
    )
    (net (code "209") (name "/VME_D5") (class "Default")
      (node (ref "IC25") (pin "20") (pinfunction "3A6_20") (pintype "bidirectional"))
    )
    (net (code "210") (name "/VME_D6") (class "Default")
      (node (ref "IC25") (pin "22") (pinfunction "3A7_22") (pintype "bidirectional"))
    )
    (net (code "211") (name "/VME_D7") (class "Default")
      (node (ref "IC25") (pin "23") (pinfunction "3A8_23") (pintype "bidirectional"))
    )
    (net (code "212") (name "/VME_D8") (class "Default")
      (node (ref "IC5") (pin "9") (pinfunction "3A1_9") (pintype "bidirectional"))
    )
    (net (code "213") (name "/VME_D9") (class "Default")
      (node (ref "IC5") (pin "12") (pinfunction "3A2_12") (pintype "bidirectional"))
    )
    (net (code "214") (name "/VME_D10") (class "Default")
      (node (ref "IC5") (pin "13") (pinfunction "3A3_13") (pintype "bidirectional"))
    )
    (net (code "215") (name "/VME_D11") (class "Default")
      (node (ref "IC5") (pin "16") (pinfunction "3A4_16") (pintype "bidirectional"))
    )
    (net (code "216") (name "/VME_D12") (class "Default")
      (node (ref "IC5") (pin "19") (pinfunction "3A5_19") (pintype "bidirectional"))
    )
    (net (code "217") (name "/VME_D13") (class "Default")
      (node (ref "IC5") (pin "20") (pinfunction "3A6_20") (pintype "bidirectional"))
    )
    (net (code "218") (name "/VME_D14") (class "Default")
      (node (ref "IC5") (pin "22") (pinfunction "3A7_22") (pintype "bidirectional"))
    )
    (net (code "219") (name "/VME_D15") (class "Default")
      (node (ref "IC5") (pin "23") (pinfunction "3A8_23") (pintype "bidirectional"))
    )
    (net (code "220") (name "/VME_D16") (class "Default")
      (node (ref "IC35") (pin "9") (pinfunction "3A1_9") (pintype "bidirectional"))
    )
    (net (code "221") (name "/VME_D17") (class "Default")
      (node (ref "IC35") (pin "12") (pinfunction "3A2_12") (pintype "bidirectional"))
    )
    (net (code "222") (name "/VME_D18") (class "Default")
      (node (ref "IC35") (pin "13") (pinfunction "3A3_13") (pintype "bidirectional"))
    )
    (net (code "223") (name "/VME_D19") (class "Default")
      (node (ref "IC35") (pin "16") (pinfunction "3A4_16") (pintype "bidirectional"))
    )
    (net (code "224") (name "/VME_D20") (class "Default")
      (node (ref "IC35") (pin "19") (pinfunction "3A5_19") (pintype "bidirectional"))
    )
    (net (code "225") (name "/VME_D21") (class "Default")
      (node (ref "IC35") (pin "20") (pinfunction "3A6_20") (pintype "bidirectional"))
    )
    (net (code "226") (name "/VME_D22") (class "Default")
      (node (ref "IC35") (pin "22") (pinfunction "3A7_22") (pintype "bidirectional"))
    )
    (net (code "227") (name "/VME_D23") (class "Default")
      (node (ref "IC35") (pin "23") (pinfunction "3A8_23") (pintype "bidirectional"))
    )
    (net (code "228") (name "/VME_D24") (class "Default")
      (node (ref "IC42") (pin "9") (pinfunction "3A1_9") (pintype "bidirectional"))
    )
    (net (code "229") (name "/VME_D25") (class "Default")
      (node (ref "IC42") (pin "12") (pinfunction "3A2_12") (pintype "bidirectional"))
    )
    (net (code "230") (name "/VME_D26") (class "Default")
      (node (ref "IC42") (pin "13") (pinfunction "3A3_13") (pintype "bidirectional"))
    )
    (net (code "231") (name "/VME_D27") (class "Default")
      (node (ref "IC42") (pin "16") (pinfunction "3A4_16") (pintype "bidirectional"))
    )
    (net (code "232") (name "/VME_D28") (class "Default")
      (node (ref "IC42") (pin "19") (pinfunction "3A5_19") (pintype "bidirectional"))
    )
    (net (code "233") (name "/VME_D29") (class "Default")
      (node (ref "IC42") (pin "20") (pinfunction "3A6_20") (pintype "bidirectional"))
    )
    (net (code "234") (name "/VME_D30") (class "Default")
      (node (ref "IC42") (pin "22") (pinfunction "3A7_22") (pintype "bidirectional"))
    )
    (net (code "235") (name "/VME_D31") (class "Default")
      (node (ref "IC42") (pin "23") (pinfunction "3A8_23") (pintype "bidirectional"))
    )
    (net (code "236") (name "/VME_DS1") (class "Default")
      (node (ref "IC22") (pin "3") (pinfunction "1Y_3") (pintype "output"))
    )
    (net (code "237") (name "/VME_DS2") (class "Default")
      (node (ref "IC22") (pin "6") (pinfunction "2Y_6") (pintype "output"))
    )
    (net (code "238") (name "/VME_DTACK") (class "Default")
      (node (ref "IC26") (pin "2") (pinfunction "1A_2") (pintype "input"))
    )
    (net (code "239") (name "/VME_DTACK_OE") (class "Default")
      (node (ref "IC26") (pin "48") (pinfunction "1OEAB_48") (pintype "input"))
    )
    (net (code "241") (name "/VME_D_DIR") (class "Default")
      (node (ref "IC25") (pin "24") (pinfunction "DIR_24") (pintype "input"))
      (node (ref "IC35") (pin "24") (pinfunction "DIR_24") (pintype "input"))
      (node (ref "IC42") (pin "24") (pinfunction "DIR_24") (pintype "input"))
      (node (ref "IC5") (pin "24") (pinfunction "DIR_24") (pintype "input"))
    )
    (net (code "242") (name "/VME_D_OE_N") (class "Default")
      (node (ref "IC35") (pin "14") (pinfunction "~{OE}_14") (pintype "input"))
      (node (ref "IC42") (pin "14") (pinfunction "~{OE}_14") (pintype "input"))
      (node (ref "IC5") (pin "14") (pinfunction "~{OE}_14") (pintype "input"))
    )
    (net (code "243") (name "/VME_GA0") (class "Default")
      (node (ref "IC27") (pin "12") (pinfunction "3A2_12") (pintype "bidirectional"))
    )
    (net (code "244") (name "/VME_GA1") (class "Default")
      (node (ref "IC27") (pin "13") (pinfunction "3A3_13") (pintype "bidirectional"))
    )
    (net (code "245") (name "/VME_GA2") (class "Default")
      (node (ref "IC27") (pin "16") (pinfunction "3A4_16") (pintype "bidirectional"))
    )
    (net (code "246") (name "/VME_GA3") (class "Default")
      (node (ref "IC27") (pin "19") (pinfunction "3A5_19") (pintype "bidirectional"))
    )
    (net (code "247") (name "/VME_GA4") (class "Default")
      (node (ref "IC27") (pin "20") (pinfunction "3A6_20") (pintype "bidirectional"))
    )
    (net (code "248") (name "/VME_GAP") (class "Default")
      (node (ref "IC27") (pin "9") (pinfunction "3A1_9") (pintype "bidirectional"))
    )
    (net (code "250") (name "/VME_IACK") (class "Default")
      (node (ref "IC25") (pin "6") (pinfunction "2Y_6") (pintype "output"))
    )
    (net (code "251") (name "/VME_IACKIN") (class "Default")
      (node (ref "IC33") (pin "3") (pinfunction "1Y_3") (pintype "output"))
      (node (ref "R209") (pin "2") (pinfunction "2_2") (pintype "passive"))
    )
    (net (code "252") (name "/VME_IACKOUT") (class "Default")
      (node (ref "IC33") (pin "5") (pinfunction "2A_5") (pintype "input"))
      (node (ref "R209") (pin "1") (pinfunction "1_1") (pintype "passive"))
    )
    (net (code "253") (name "/VME_IRQ1") (class "Default")
      (node (ref "IC25") (pin "48") (pinfunction "1OEAB_48") (pintype "input"))
      (node (ref "R174") (pin "1") (pinfunction "1_1") (pintype "passive"))
    )
    (net (code "254") (name "/VME_IRQ2") (class "Default")
      (node (ref "IC5") (pin "41") (pinfunction "2OEAB_41") (pintype "input"))
      (node (ref "R191") (pin "1") (pinfunction "1_1") (pintype "passive"))
    )
    (net (code "255") (name "/VME_IRQ3") (class "Default")
      (node (ref "IC5") (pin "48") (pinfunction "1OEAB_48") (pintype "input"))
      (node (ref "R190") (pin "1") (pinfunction "1_1") (pintype "passive"))
    )
    (net (code "256") (name "/VME_IRQ4") (class "Default")
      (node (ref "IC42") (pin "41") (pinfunction "2OEAB_41") (pintype "input"))
      (node (ref "R185") (pin "1") (pinfunction "1_1") (pintype "passive"))
    )
    (net (code "257") (name "/VME_IRQ5") (class "Default")
      (node (ref "IC42") (pin "48") (pinfunction "1OEAB_48") (pintype "input"))
      (node (ref "R179") (pin "1") (pinfunction "1_1") (pintype "passive"))
    )
    (net (code "258") (name "/VME_IRQ6") (class "Default")
      (node (ref "IC35") (pin "41") (pinfunction "2OEAB_41") (pintype "input"))
      (node (ref "R177") (pin "1") (pinfunction "1_1") (pintype "passive"))
    )
    (net (code "259") (name "/VME_IRQ7") (class "Default")
      (node (ref "IC35") (pin "48") (pinfunction "1OEAB_48") (pintype "input"))
      (node (ref "R176") (pin "1") (pinfunction "1_1") (pintype "passive"))
    )
    (net (code "261") (name "/VME_LWORD") (class "Default")
      (node (ref "IC22") (pin "23") (pinfunction "3A8_23") (pintype "bidirectional"))
    )
    (net (code "262") (name "/VME_RETRY") (class "Default")
      (node (ref "IC15") (pin "2") (pinfunction "1A_2") (pintype "input"))
    )
    (net (code "263") (name "/VME_RETRY_OE") (class "Default")
      (node (ref "IC15") (pin "48") (pinfunction "1OEAB_48") (pintype "input"))
      (node (ref "R210") (pin "2") (pinfunction "2_2") (pintype "passive"))
    )
    (net (code "264") (name "/VME_SYSCLK") (class "Default")
      (node (ref "IC21") (pin "3") (pinfunction "1Y_3") (pintype "output"))
    )
    (net (code "265") (name "/VME_SYSRESET") (class "Default")
      (node (ref "IC15") (pin "22") (pinfunction "3A7_22") (pintype "bidirectional"))
    )
    (net (code "266") (name "/VME_TCK") (class "Default")
      (node (ref "IC15") (pin "23") (pinfunction "3A8_23") (pintype "bidirectional"))
    )
    (net (code "267") (name "/VME_TDI") (class "Default")
      (node (ref "IC27") (pin "22") (pinfunction "3A7_22") (pintype "bidirectional"))
    )
    (net (code "268") (name "/VME_TDO") (class "Default")
      (node (ref "IC27") (pin "5") (pinfunction "2A_5") (pintype "input"))
    )
    (net (code "269") (name "/VME_TDO_OE") (class "Default")
      (node (ref "IC27") (pin "41") (pinfunction "2OEAB_41") (pintype "input"))
    )
    (net (code "270") (name "/VME_TMS") (class "Default")
      (node (ref "IC27") (pin "23") (pinfunction "3A8_23") (pintype "bidirectional"))
    )
    (net (code "271") (name "/VME_TRST") (class "Default")
      (node (ref "IC27") (pin "3") (pinfunction "1Y_3") (pintype "output"))
    )
    (net (code "272") (name "/VME_WRITE") (class "Default")
      (node (ref "IC26") (pin "6") (pinfunction "2Y_6") (pintype "output"))
    )
    (net (code "273") (name "GND") (class "Default")
      (node (ref "C125") (pin "2") (pinfunction "2_2") (pintype "passive"))
      (node (ref "C127") (pin "2") (pinfunction "2_2") (pintype "passive"))
      (node (ref "C132") (pin "2") (pinfunction "2_2") (pintype "passive"))
      (node (ref "C153") (pin "2") (pinfunction "2_2") (pintype "passive"))
      (node (ref "C154") (pin "1") (pinfunction "1_1") (pintype "passive"))
      (node (ref "C164") (pin "2") (pinfunction "2_2") (pintype "passive"))
      (node (ref "C184") (pin "1") (pinfunction "1_1") (pintype "passive"))
      (node (ref "C185") (pin "2") (pinfunction "2_2") (pintype "passive"))
      (node (ref "C226") (pin "1") (pinfunction "1_1") (pintype "passive"))
      (node (ref "C227") (pin "1") (pinfunction "1_1") (pintype "passive"))
      (node (ref "C240") (pin "2") (pinfunction "2_2") (pintype "passive"))
      (node (ref "C244") (pin "1") (pinfunction "1_1") (pintype "passive"))
      (node (ref "C245") (pin "1") (pinfunction "1_1") (pintype "passive"))
      (node (ref "C246") (pin "1") (pinfunction "1_1") (pintype "passive"))
      (node (ref "C247") (pin "2") (pinfunction "2_2") (pintype "passive"))
      (node (ref "C248") (pin "2") (pinfunction "2_2") (pintype "passive"))
      (node (ref "C249") (pin "2") (pinfunction "2_2") (pintype "passive"))
      (node (ref "C250") (pin "1") (pinfunction "1_1") (pintype "passive"))
      (node (ref "C251") (pin "1") (pinfunction "1_1") (pintype "passive"))
      (node (ref "C252") (pin "1") (pinfunction "1_1") (pintype "passive"))
      (node (ref "C253") (pin "2") (pinfunction "2_2") (pintype "passive"))
      (node (ref "C254") (pin "1") (pinfunction "1_1") (pintype "passive"))
      (node (ref "C257") (pin "1") (pinfunction "1_1") (pintype "passive"))
      (node (ref "C264") (pin "2") (pinfunction "2_2") (pintype "passive"))
      (node (ref "C287") (pin "2") (pinfunction "2_2") (pintype "passive"))
      (node (ref "C292") (pin "1") (pinfunction "1_1") (pintype "passive"))
      (node (ref "C293") (pin "1") (pinfunction "1_1") (pintype "passive"))
      (node (ref "C294") (pin "2") (pinfunction "2_2") (pintype "passive"))
      (node (ref "C295") (pin "1") (pinfunction "1_1") (pintype "passive"))
      (node (ref "C296") (pin "2") (pinfunction "2_2") (pintype "passive"))
      (node (ref "C318") (pin "1") (pinfunction "1_1") (pintype "passive"))
      (node (ref "C319") (pin "2") (pinfunction "2_2") (pintype "passive"))
      (node (ref "C326") (pin "2") (pinfunction "2_2") (pintype "passive"))
      (node (ref "C327") (pin "1") (pinfunction "1_1") (pintype "passive"))
      (node (ref "C328") (pin "2") (pinfunction "2_2") (pintype "passive"))
      (node (ref "C329") (pin "1") (pinfunction "1_1") (pintype "passive"))
      (node (ref "C331") (pin "2") (pinfunction "2_2") (pintype "passive"))
      (node (ref "C332") (pin "1") (pinfunction "1_1") (pintype "passive"))
      (node (ref "C335") (pin "1") (pinfunction "1_1") (pintype "passive"))
      (node (ref "C336") (pin "2") (pinfunction "2_2") (pintype "passive"))
      (node (ref "C337") (pin "1") (pinfunction "1_1") (pintype "passive"))
      (node (ref "C338") (pin "2") (pinfunction "2_2") (pintype "passive"))
      (node (ref "C436") (pin "2") (pinfunction "2_2") (pintype "passive"))
      (node (ref "C437") (pin "1") (pinfunction "1_1") (pintype "passive"))
      (node (ref "C447") (pin "2") (pinfunction "2_2") (pintype "passive"))
      (node (ref "C457") (pin "1") (pinfunction "1_1") (pintype "passive"))
      (node (ref "C464") (pin "2") (pinfunction "2_2") (pintype "passive"))
      (node (ref "C465") (pin "1") (pinfunction "1_1") (pintype "passive"))
      (node (ref "C500") (pin "1") (pinfunction "1_1") (pintype "passive"))
      (node (ref "C501") (pin "2") (pinfunction "2_2") (pintype "passive"))
      (node (ref "C506") (pin "1") (pinfunction "1_1") (pintype "passive"))
      (node (ref "C507") (pin "2") (pinfunction "2_2") (pintype "passive"))
      (node (ref "C512") (pin "1") (pinfunction "1_1") (pintype "passive"))
      (node (ref "C513") (pin "2") (pinfunction "2_2") (pintype "passive"))
      (node (ref "C516") (pin "1") (pinfunction "1_1") (pintype "passive"))
      (node (ref "C517") (pin "2") (pinfunction "2_2") (pintype "passive"))
      (node (ref "C519") (pin "2") (pinfunction "2_2") (pintype "passive"))
      (node (ref "C520") (pin "1") (pinfunction "1_1") (pintype "passive"))
      (node (ref "C521") (pin "2") (pinfunction "2_2") (pintype "passive"))
      (node (ref "C522") (pin "1") (pinfunction "1_1") (pintype "passive"))
      (node (ref "IC15") (pin "10") (pinfunction "GND_10") (pintype "power_in"))
      (node (ref "IC15") (pin "14") (pinfunction "~{OE}_14") (pintype "input"))
      (node (ref "IC15") (pin "15") (pinfunction "GND_15") (pintype "power_in"))
      (node (ref "IC15") (pin "17") (pinfunction "CLKBA_17") (pintype "input"))
      (node (ref "IC15") (pin "21") (pinfunction "GND_21") (pintype "power_in"))
      (node (ref "IC15") (pin "24") (pinfunction "DIR_24") (pintype "input"))
      (node (ref "IC15") (pin "28") (pinfunction "GND_28") (pintype "power_in"))
      (node (ref "IC15") (pin "32") (pinfunction "CLKAB_32") (pintype "input"))
      (node (ref "IC15") (pin "34") (pinfunction "GND_34") (pintype "power_in"))
      (node (ref "IC15") (pin "39") (pinfunction "GND_39") (pintype "power_in"))
      (node (ref "IC15") (pin "4") (pinfunction "GND_4") (pintype "power_in"))
      (node (ref "IC15") (pin "45") (pinfunction "GND_45") (pintype "input"))
      (node (ref "IC15") (pin "5") (pinfunction "2A_5") (pintype "input"))
      (node (ref "IC21") (pin "1") (pinfunction "~{1OEBY}_1") (pintype "input"))
      (node (ref "IC21") (pin "10") (pinfunction "GND_10") (pintype "power_in"))
      (node (ref "IC21") (pin "15") (pinfunction "GND_15") (pintype "power_in"))
      (node (ref "IC21") (pin "17") (pinfunction "CLKBA_17") (pintype "input"))
      (node (ref "IC21") (pin "2") (pinfunction "1A_2") (pintype "input"))
      (node (ref "IC21") (pin "21") (pinfunction "GND_21") (pintype "power_in"))
      (node (ref "IC21") (pin "28") (pinfunction "GND_28") (pintype "power_in"))
      (node (ref "IC21") (pin "32") (pinfunction "CLKAB_32") (pintype "input"))
      (node (ref "IC21") (pin "34") (pinfunction "GND_34") (pintype "power_in"))
      (node (ref "IC21") (pin "39") (pinfunction "GND_39") (pintype "power_in"))
      (node (ref "IC21") (pin "4") (pinfunction "GND_4") (pintype "power_in"))
      (node (ref "IC21") (pin "41") (pinfunction "2OEAB_41") (pintype "input"))
      (node (ref "IC21") (pin "45") (pinfunction "GND_45") (pintype "input"))
      (node (ref "IC21") (pin "48") (pinfunction "1OEAB_48") (pintype "input"))
      (node (ref "IC21") (pin "5") (pinfunction "2A_5") (pintype "input"))
      (node (ref "IC21") (pin "8") (pinfunction "2~{OEBY}_8") (pintype "input"))
      (node (ref "IC22") (pin "1") (pinfunction "~{1OEBY}_1") (pintype "input"))
      (node (ref "IC22") (pin "10") (pinfunction "GND_10") (pintype "power_in"))
      (node (ref "IC22") (pin "15") (pinfunction "GND_15") (pintype "power_in"))
      (node (ref "IC22") (pin "17") (pinfunction "CLKBA_17") (pintype "input"))
      (node (ref "IC22") (pin "2") (pinfunction "1A_2") (pintype "input"))
      (node (ref "IC22") (pin "21") (pinfunction "GND_21") (pintype "power_in"))
      (node (ref "IC22") (pin "28") (pinfunction "GND_28") (pintype "power_in"))
      (node (ref "IC22") (pin "32") (pinfunction "CLKAB_32") (pintype "input"))
      (node (ref "IC22") (pin "34") (pinfunction "GND_34") (pintype "power_in"))
      (node (ref "IC22") (pin "39") (pinfunction "GND_39") (pintype "power_in"))
      (node (ref "IC22") (pin "4") (pinfunction "GND_4") (pintype "power_in"))
      (node (ref "IC22") (pin "41") (pinfunction "2OEAB_41") (pintype "input"))
      (node (ref "IC22") (pin "45") (pinfunction "GND_45") (pintype "input"))
      (node (ref "IC22") (pin "48") (pinfunction "1OEAB_48") (pintype "input"))
      (node (ref "IC22") (pin "5") (pinfunction "2A_5") (pintype "input"))
      (node (ref "IC22") (pin "8") (pinfunction "2~{OEBY}_8") (pintype "input"))
      (node (ref "IC25") (pin "10") (pinfunction "GND_10") (pintype "power_in"))
      (node (ref "IC25") (pin "15") (pinfunction "GND_15") (pintype "power_in"))
      (node (ref "IC25") (pin "17") (pinfunction "CLKBA_17") (pintype "input"))
      (node (ref "IC25") (pin "2") (pinfunction "1A_2") (pintype "input"))
      (node (ref "IC25") (pin "21") (pinfunction "GND_21") (pintype "power_in"))
      (node (ref "IC25") (pin "28") (pinfunction "GND_28") (pintype "power_in"))
      (node (ref "IC25") (pin "32") (pinfunction "CLKAB_32") (pintype "input"))
      (node (ref "IC25") (pin "34") (pinfunction "GND_34") (pintype "power_in"))
      (node (ref "IC25") (pin "39") (pinfunction "GND_39") (pintype "power_in"))
      (node (ref "IC25") (pin "4") (pinfunction "GND_4") (pintype "power_in"))
      (node (ref "IC25") (pin "41") (pinfunction "2OEAB_41") (pintype "input"))
      (node (ref "IC25") (pin "45") (pinfunction "GND_45") (pintype "input"))
      (node (ref "IC25") (pin "5") (pinfunction "2A_5") (pintype "input"))
      (node (ref "IC25") (pin "8") (pinfunction "2~{OEBY}_8") (pintype "input"))
      (node (ref "IC26") (pin "10") (pinfunction "GND_10") (pintype "power_in"))
      (node (ref "IC26") (pin "15") (pinfunction "GND_15") (pintype "power_in"))
      (node (ref "IC26") (pin "17") (pinfunction "CLKBA_17") (pintype "input"))
      (node (ref "IC26") (pin "21") (pinfunction "GND_21") (pintype "power_in"))
      (node (ref "IC26") (pin "28") (pinfunction "GND_28") (pintype "power_in"))
      (node (ref "IC26") (pin "32") (pinfunction "CLKAB_32") (pintype "input"))
      (node (ref "IC26") (pin "34") (pinfunction "GND_34") (pintype "power_in"))
      (node (ref "IC26") (pin "39") (pinfunction "GND_39") (pintype "power_in"))
      (node (ref "IC26") (pin "4") (pinfunction "GND_4") (pintype "power_in"))
      (node (ref "IC26") (pin "41") (pinfunction "2OEAB_41") (pintype "input"))
      (node (ref "IC26") (pin "45") (pinfunction "GND_45") (pintype "input"))
      (node (ref "IC26") (pin "5") (pinfunction "2A_5") (pintype "input"))
      (node (ref "IC26") (pin "8") (pinfunction "2~{OEBY}_8") (pintype "input"))
      (node (ref "IC27") (pin "1") (pinfunction "~{1OEBY}_1") (pintype "input"))
      (node (ref "IC27") (pin "10") (pinfunction "GND_10") (pintype "power_in"))
      (node (ref "IC27") (pin "14") (pinfunction "~{OE}_14") (pintype "input"))
      (node (ref "IC27") (pin "15") (pinfunction "GND_15") (pintype "power_in"))
      (node (ref "IC27") (pin "17") (pinfunction "CLKBA_17") (pintype "input"))
      (node (ref "IC27") (pin "2") (pinfunction "1A_2") (pintype "input"))
      (node (ref "IC27") (pin "21") (pinfunction "GND_21") (pintype "power_in"))
      (node (ref "IC27") (pin "24") (pinfunction "DIR_24") (pintype "input"))
      (node (ref "IC27") (pin "28") (pinfunction "GND_28") (pintype "power_in"))
      (node (ref "IC27") (pin "32") (pinfunction "CLKAB_32") (pintype "input"))
      (node (ref "IC27") (pin "34") (pinfunction "GND_34") (pintype "power_in"))
      (node (ref "IC27") (pin "39") (pinfunction "GND_39") (pintype "power_in"))
      (node (ref "IC27") (pin "4") (pinfunction "GND_4") (pintype "power_in"))
      (node (ref "IC27") (pin "45") (pinfunction "GND_45") (pintype "input"))
      (node (ref "IC27") (pin "48") (pinfunction "1OEAB_48") (pintype "input"))
      (node (ref "IC33") (pin "1") (pinfunction "~{1OEBY}_1") (pintype "input"))
      (node (ref "IC33") (pin "10") (pinfunction "GND_10") (pintype "power_in"))
      (node (ref "IC33") (pin "15") (pinfunction "GND_15") (pintype "power_in"))
      (node (ref "IC33") (pin "17") (pinfunction "CLKBA_17") (pintype "input"))
      (node (ref "IC33") (pin "2") (pinfunction "1A_2") (pintype "input"))
      (node (ref "IC33") (pin "21") (pinfunction "GND_21") (pintype "power_in"))
      (node (ref "IC33") (pin "28") (pinfunction "GND_28") (pintype "power_in"))
      (node (ref "IC33") (pin "32") (pinfunction "CLKAB_32") (pintype "input"))
      (node (ref "IC33") (pin "34") (pinfunction "GND_34") (pintype "power_in"))
      (node (ref "IC33") (pin "39") (pinfunction "GND_39") (pintype "power_in"))
      (node (ref "IC33") (pin "4") (pinfunction "GND_4") (pintype "power_in"))
      (node (ref "IC33") (pin "45") (pinfunction "GND_45") (pintype "input"))
      (node (ref "IC33") (pin "48") (pinfunction "1OEAB_48") (pintype "input"))
      (node (ref "IC35") (pin "10") (pinfunction "GND_10") (pintype "power_in"))
      (node (ref "IC35") (pin "15") (pinfunction "GND_15") (pintype "power_in"))
      (node (ref "IC35") (pin "17") (pinfunction "CLKBA_17") (pintype "input"))
      (node (ref "IC35") (pin "2") (pinfunction "1A_2") (pintype "input"))
      (node (ref "IC35") (pin "21") (pinfunction "GND_21") (pintype "power_in"))
      (node (ref "IC35") (pin "28") (pinfunction "GND_28") (pintype "power_in"))
      (node (ref "IC35") (pin "32") (pinfunction "CLKAB_32") (pintype "input"))
      (node (ref "IC35") (pin "34") (pinfunction "GND_34") (pintype "power_in"))
      (node (ref "IC35") (pin "39") (pinfunction "GND_39") (pintype "power_in"))
      (node (ref "IC35") (pin "4") (pinfunction "GND_4") (pintype "power_in"))
      (node (ref "IC35") (pin "45") (pinfunction "GND_45") (pintype "input"))
      (node (ref "IC35") (pin "5") (pinfunction "2A_5") (pintype "input"))
      (node (ref "IC42") (pin "10") (pinfunction "GND_10") (pintype "power_in"))
      (node (ref "IC42") (pin "15") (pinfunction "GND_15") (pintype "power_in"))
      (node (ref "IC42") (pin "17") (pinfunction "CLKBA_17") (pintype "input"))
      (node (ref "IC42") (pin "2") (pinfunction "1A_2") (pintype "input"))
      (node (ref "IC42") (pin "21") (pinfunction "GND_21") (pintype "power_in"))
      (node (ref "IC42") (pin "28") (pinfunction "GND_28") (pintype "power_in"))
      (node (ref "IC42") (pin "32") (pinfunction "CLKAB_32") (pintype "input"))
      (node (ref "IC42") (pin "34") (pinfunction "GND_34") (pintype "power_in"))
      (node (ref "IC42") (pin "39") (pinfunction "GND_39") (pintype "power_in"))
      (node (ref "IC42") (pin "4") (pinfunction "GND_4") (pintype "power_in"))
      (node (ref "IC42") (pin "45") (pinfunction "GND_45") (pintype "input"))
      (node (ref "IC42") (pin "5") (pinfunction "2A_5") (pintype "input"))
      (node (ref "IC5") (pin "10") (pinfunction "GND_10") (pintype "power_in"))
      (node (ref "IC5") (pin "15") (pinfunction "GND_15") (pintype "power_in"))
      (node (ref "IC5") (pin "17") (pinfunction "CLKBA_17") (pintype "input"))
      (node (ref "IC5") (pin "2") (pinfunction "1A_2") (pintype "input"))
      (node (ref "IC5") (pin "21") (pinfunction "GND_21") (pintype "power_in"))
      (node (ref "IC5") (pin "28") (pinfunction "GND_28") (pintype "power_in"))
      (node (ref "IC5") (pin "32") (pinfunction "CLKAB_32") (pintype "input"))
      (node (ref "IC5") (pin "34") (pinfunction "GND_34") (pintype "power_in"))
      (node (ref "IC5") (pin "39") (pinfunction "GND_39") (pintype "power_in"))
      (node (ref "IC5") (pin "4") (pinfunction "GND_4") (pintype "power_in"))
      (node (ref "IC5") (pin "45") (pinfunction "GND_45") (pintype "input"))
      (node (ref "IC5") (pin "5") (pinfunction "2A_5") (pintype "input"))
      (node (ref "P1") (pin "MTG1") (pinfunction "MTG1_MTG1") (pintype "passive"))
      (node (ref "P1") (pin "MTG2") (pinfunction "MTG2_MTG2") (pintype "passive"))
      (node (ref "P1") (pin "a11") (pinfunction "a11_a11") (pintype "bidirectional"))
      (node (ref "P1") (pin "a15") (pinfunction "a15_a15") (pintype "bidirectional"))
      (node (ref "P1") (pin "a17") (pinfunction "a17_a17") (pintype "bidirectional"))
      (node (ref "P1") (pin "a19") (pinfunction "a19_a19") (pintype "bidirectional"))
      (node (ref "P1") (pin "a9") (pinfunction "a9_a9") (pintype "bidirectional"))
      (node (ref "P1") (pin "b20") (pinfunction "b20_b20") (pintype "bidirectional"))
      (node (ref "P1") (pin "b23") (pinfunction "b23_b23") (pintype "bidirectional"))
      (node (ref "P1") (pin "c9") (pinfunction "c9_c9") (pintype "bidirectional"))
      (node (ref "P1") (pin "d2") (pinfunction "d2_d2") (pintype "bidirectional"))
      (node (ref "P1") (pin "d31") (pinfunction "d31_d31") (pintype "bidirectional"))
      (node (ref "P1") (pin "z10") (pinfunction "z10_z10") (pintype "bidirectional"))
      (node (ref "P1") (pin "z12") (pinfunction "z12_z12") (pintype "bidirectional"))
      (node (ref "P1") (pin "z14") (pinfunction "z14_z14") (pintype "bidirectional"))
      (node (ref "P1") (pin "z16") (pinfunction "z16_z16") (pintype "bidirectional"))
      (node (ref "P1") (pin "z18") (pinfunction "z18_z18") (pintype "bidirectional"))
      (node (ref "P1") (pin "z2") (pinfunction "z2_z2") (pintype "bidirectional"))
      (node (ref "P1") (pin "z20") (pinfunction "z20_z20") (pintype "bidirectional"))
      (node (ref "P1") (pin "z22") (pinfunction "z22_z22") (pintype "bidirectional"))
      (node (ref "P1") (pin "z24") (pinfunction "z24_z24") (pintype "bidirectional"))
      (node (ref "P1") (pin "z26") (pinfunction "z26_z26") (pintype "bidirectional"))
      (node (ref "P1") (pin "z28") (pinfunction "z28_z28") (pintype "bidirectional"))
      (node (ref "P1") (pin "z30") (pinfunction "z30_z30") (pintype "bidirectional"))
      (node (ref "P1") (pin "z32") (pinfunction "z32_z32") (pintype "bidirectional"))
      (node (ref "P1") (pin "z4") (pinfunction "z4_z4") (pintype "bidirectional"))
      (node (ref "P1") (pin "z6") (pinfunction "z6_z6") (pintype "bidirectional"))
      (node (ref "P1") (pin "z8") (pinfunction "z8_z8") (pintype "bidirectional"))
      (node (ref "P3") (pin "MTG1") (pinfunction "MTG1_MTG1") (pintype "passive"))
      (node (ref "P3") (pin "MTG2") (pinfunction "MTG2_MTG2") (pintype "passive"))
      (node (ref "P3") (pin "a1") (pinfunction "a1_a1") (pintype "bidirectional"))
      (node (ref "P3") (pin "a10") (pinfunction "a10_a10") (pintype "bidirectional"))
      (node (ref "P3") (pin "a13") (pinfunction "a13_a13") (pintype "bidirectional"))
      (node (ref "P3") (pin "a16") (pinfunction "a16_a16") (pintype "bidirectional"))
      (node (ref "P3") (pin "a19") (pinfunction "a19_a19") (pintype "bidirectional"))
      (node (ref "P3") (pin "a22") (pinfunction "a22_a22") (pintype "bidirectional"))
      (node (ref "P3") (pin "a25") (pinfunction "a25_a25") (pintype "bidirectional"))
      (node (ref "P3") (pin "a28") (pinfunction "a28_a28") (pintype "bidirectional"))
      (node (ref "P3") (pin "a31") (pinfunction "a31_a31") (pintype "bidirectional"))
      (node (ref "P3") (pin "a32") (pinfunction "a32_a32") (pintype "bidirectional"))
      (node (ref "P3") (pin "a4") (pinfunction "a4_a4") (pintype "bidirectional"))
      (node (ref "P3") (pin "a7") (pinfunction "a7_a7") (pintype "bidirectional"))
      (node (ref "P3") (pin "b12") (pinfunction "b12_b12") (pintype "bidirectional"))
      (node (ref "P3") (pin "b2") (pinfunction "b2_b2") (pintype "bidirectional"))
      (node (ref "P3") (pin "b22") (pinfunction "b22_b22") (pintype "bidirectional"))
      (node (ref "P3") (pin "b31") (pinfunction "b31_b31") (pintype "bidirectional"))
      (node (ref "P3") (pin "c23") (pinfunction "c23_c23") (pintype "bidirectional"))
      (node (ref "P3") (pin "c24") (pinfunction "c24_c24") (pintype "bidirectional"))
      (node (ref "P3") (pin "c27") (pinfunction "c27_c27") (pintype "bidirectional"))
      (node (ref "P3") (pin "c28") (pinfunction "c28_c28") (pintype "bidirectional"))
      (node (ref "P3") (pin "c31") (pinfunction "c31_c31") (pintype "bidirectional"))
      (node (ref "P3") (pin "c32") (pinfunction "c32_c32") (pintype "bidirectional"))
      (node (ref "P3") (pin "d1") (pinfunction "d1_d1") (pintype "bidirectional"))
      (node (ref "P3") (pin "d10") (pinfunction "d10_d10") (pintype "bidirectional"))
      (node (ref "P3") (pin "d13") (pinfunction "d13_d13") (pintype "bidirectional"))
      (node (ref "P3") (pin "d16") (pinfunction "d16_d16") (pintype "bidirectional"))
      (node (ref "P3") (pin "d19") (pinfunction "d19_d19") (pintype "bidirectional"))
      (node (ref "P3") (pin "d22") (pinfunction "d22_d22") (pintype "bidirectional"))
      (node (ref "P3") (pin "d25") (pinfunction "d25_d25") (pintype "bidirectional"))
      (node (ref "P3") (pin "d28") (pinfunction "d28_d28") (pintype "bidirectional"))
      (node (ref "P3") (pin "d31") (pinfunction "d31_d31") (pintype "bidirectional"))
      (node (ref "P3") (pin "d4") (pinfunction "d4_d4") (pintype "bidirectional"))
      (node (ref "P3") (pin "d7") (pinfunction "d7_d7") (pintype "bidirectional"))
      (node (ref "P3") (pin "z10") (pinfunction "z10_z10") (pintype "bidirectional"))
      (node (ref "P3") (pin "z12") (pinfunction "z12_z12") (pintype "bidirectional"))
      (node (ref "P3") (pin "z14") (pinfunction "z14_z14") (pintype "bidirectional"))
      (node (ref "P3") (pin "z16") (pinfunction "z16_z16") (pintype "bidirectional"))
      (node (ref "P3") (pin "z18") (pinfunction "z18_z18") (pintype "bidirectional"))
      (node (ref "P3") (pin "z2") (pinfunction "z2_z2") (pintype "bidirectional"))
      (node (ref "P3") (pin "z20") (pinfunction "z20_z20") (pintype "bidirectional"))
      (node (ref "P3") (pin "z22") (pinfunction "z22_z22") (pintype "bidirectional"))
      (node (ref "P3") (pin "z24") (pinfunction "z24_z24") (pintype "bidirectional"))
      (node (ref "P3") (pin "z26") (pinfunction "z26_z26") (pintype "bidirectional"))
      (node (ref "P3") (pin "z28") (pinfunction "z28_z28") (pintype "bidirectional"))
      (node (ref "P3") (pin "z30") (pinfunction "z30_z30") (pintype "bidirectional"))
      (node (ref "P3") (pin "z32") (pinfunction "z32_z32") (pintype "bidirectional"))
      (node (ref "P3") (pin "z4") (pinfunction "z4_z4") (pintype "bidirectional"))
      (node (ref "P3") (pin "z6") (pinfunction "z6_z6") (pintype "bidirectional"))
      (node (ref "P3") (pin "z8") (pinfunction "z8_z8") (pintype "bidirectional"))
      (node (ref "R174") (pin "2") (pinfunction "2_2") (pintype "passive"))
      (node (ref "R176") (pin "2") (pinfunction "2_2") (pintype "passive"))
      (node (ref "R177") (pin "2") (pinfunction "2_2") (pintype "passive"))
      (node (ref "R179") (pin "2") (pinfunction "2_2") (pintype "passive"))
      (node (ref "R185") (pin "2") (pinfunction "2_2") (pintype "passive"))
      (node (ref "R190") (pin "2") (pinfunction "2_2") (pintype "passive"))
      (node (ref "R191") (pin "2") (pinfunction "2_2") (pintype "passive"))
      (node (ref "R210") (pin "1") (pinfunction "1_1") (pintype "passive"))
      (node (ref "R211") (pin "1") (pinfunction "1_1") (pintype "passive"))
    )
    (net (code "274") (name "M12V_VME") (class "Default")
      (node (ref "P1") (pin "a31") (pinfunction "a31_a31") (pintype "bidirectional"))
    )
    (net (code "275") (name "P3V3") (class "Default")
      (node (ref "C125") (pin "1") (pinfunction "1_1") (pintype "passive"))
      (node (ref "C127") (pin "1") (pinfunction "1_1") (pintype "passive"))
      (node (ref "C132") (pin "1") (pinfunction "1_1") (pintype "passive"))
      (node (ref "C153") (pin "1") (pinfunction "1_1") (pintype "passive"))
      (node (ref "C154") (pin "2") (pinfunction "2_2") (pintype "passive"))
      (node (ref "C164") (pin "1") (pinfunction "1_1") (pintype "passive"))
      (node (ref "C184") (pin "2") (pinfunction "2_2") (pintype "passive"))
      (node (ref "C185") (pin "1") (pinfunction "1_1") (pintype "passive"))
      (node (ref "C226") (pin "2") (pinfunction "2_2") (pintype "passive"))
      (node (ref "C227") (pin "2") (pinfunction "2_2") (pintype "passive"))
      (node (ref "C240") (pin "1") (pinfunction "1_1") (pintype "passive"))
      (node (ref "C244") (pin "2") (pinfunction "2_2") (pintype "passive"))
      (node (ref "C245") (pin "2") (pinfunction "2_2") (pintype "passive"))
      (node (ref "C246") (pin "2") (pinfunction "2_2") (pintype "passive"))
      (node (ref "C247") (pin "1") (pinfunction "1_1") (pintype "passive"))
      (node (ref "C248") (pin "1") (pinfunction "1_1") (pintype "passive"))
      (node (ref "C249") (pin "1") (pinfunction "1_1") (pintype "passive"))
      (node (ref "C250") (pin "2") (pinfunction "2_2") (pintype "passive"))
      (node (ref "C251") (pin "2") (pinfunction "2_2") (pintype "passive"))
      (node (ref "C252") (pin "2") (pinfunction "2_2") (pintype "passive"))
      (node (ref "C253") (pin "1") (pinfunction "1_1") (pintype "passive"))
      (node (ref "C254") (pin "2") (pinfunction "2_2") (pintype "passive"))
      (node (ref "C257") (pin "2") (pinfunction "2_2") (pintype "passive"))
      (node (ref "C264") (pin "1") (pinfunction "1_1") (pintype "passive"))
      (node (ref "C287") (pin "1") (pinfunction "1_1") (pintype "passive"))
      (node (ref "C292") (pin "2") (pinfunction "2_2") (pintype "passive"))
      (node (ref "C293") (pin "2") (pinfunction "2_2") (pintype "passive"))
      (node (ref "C294") (pin "1") (pinfunction "1_1") (pintype "passive"))
      (node (ref "C295") (pin "2") (pinfunction "2_2") (pintype "passive"))
      (node (ref "C296") (pin "1") (pinfunction "1_1") (pintype "passive"))
      (node (ref "C318") (pin "2") (pinfunction "2_2") (pintype "passive"))
      (node (ref "C319") (pin "1") (pinfunction "1_1") (pintype "passive"))
      (node (ref "C326") (pin "1") (pinfunction "1_1") (pintype "passive"))
      (node (ref "C327") (pin "2") (pinfunction "2_2") (pintype "passive"))
      (node (ref "C328") (pin "1") (pinfunction "1_1") (pintype "passive"))
      (node (ref "C329") (pin "2") (pinfunction "2_2") (pintype "passive"))
      (node (ref "C331") (pin "1") (pinfunction "1_1") (pintype "passive"))
      (node (ref "C332") (pin "2") (pinfunction "2_2") (pintype "passive"))
      (node (ref "C335") (pin "2") (pinfunction "2_2") (pintype "passive"))
      (node (ref "C336") (pin "1") (pinfunction "1_1") (pintype "passive"))
      (node (ref "C337") (pin "2") (pinfunction "2_2") (pintype "passive"))
      (node (ref "C338") (pin "1") (pinfunction "1_1") (pintype "passive"))
      (node (ref "C436") (pin "1") (pinfunction "1_1") (pintype "passive"))
      (node (ref "C437") (pin "2") (pinfunction "2_2") (pintype "passive"))
      (node (ref "C447") (pin "1") (pinfunction "1_1") (pintype "passive"))
      (node (ref "C457") (pin "2") (pinfunction "2_2") (pintype "passive"))
      (node (ref "C464") (pin "1") (pinfunction "1_1") (pintype "passive"))
      (node (ref "C465") (pin "2") (pinfunction "2_2") (pintype "passive"))
      (node (ref "C500") (pin "2") (pinfunction "2_2") (pintype "passive"))
      (node (ref "C501") (pin "1") (pinfunction "1_1") (pintype "passive"))
      (node (ref "C506") (pin "2") (pinfunction "2_2") (pintype "passive"))
      (node (ref "C507") (pin "1") (pinfunction "1_1") (pintype "passive"))
      (node (ref "C512") (pin "2") (pinfunction "2_2") (pintype "passive"))
      (node (ref "C513") (pin "1") (pinfunction "1_1") (pintype "passive"))
      (node (ref "C516") (pin "2") (pinfunction "2_2") (pintype "passive"))
      (node (ref "C517") (pin "1") (pinfunction "1_1") (pintype "passive"))
      (node (ref "C519") (pin "1") (pinfunction "1_1") (pintype "passive"))
      (node (ref "C520") (pin "2") (pinfunction "2_2") (pintype "passive"))
      (node (ref "C521") (pin "1") (pinfunction "1_1") (pintype "passive"))
      (node (ref "C522") (pin "2") (pinfunction "2_2") (pintype "passive"))
      (node (ref "IC15") (pin "1") (pinfunction "~{1OEBY}_1") (pintype "input"))
      (node (ref "IC15") (pin "11") (pinfunction "LE_11") (pintype "input"))
      (node (ref "IC15") (pin "18") (pinfunction "VCC_18") (pintype "power_in"))
      (node (ref "IC15") (pin "25") (pinfunction "VCC_25") (pintype "power_in"))
      (node (ref "IC15") (pin "31") (pinfunction "VCC_31") (pintype "power_in"))
      (node (ref "IC15") (pin "35") (pinfunction "VCC_35") (pintype "power_in"))
      (node (ref "IC15") (pin "38") (pinfunction "VCC_38") (pintype "power_in"))
      (node (ref "IC15") (pin "42") (pinfunction "VCC_42") (pintype "power_in"))
      (node (ref "IC15") (pin "44") (pinfunction "BIASVCC_44") (pintype "input"))
      (node (ref "IC15") (pin "47") (pinfunction "VCC_47") (pintype "input"))
      (node (ref "IC15") (pin "7") (pinfunction "VCC_7") (pintype "power_in"))
      (node (ref "IC15") (pin "8") (pinfunction "2~{OEBY}_8") (pintype "input"))
      (node (ref "IC21") (pin "11") (pinfunction "LE_11") (pintype "input"))
      (node (ref "IC21") (pin "18") (pinfunction "VCC_18") (pintype "power_in"))
      (node (ref "IC21") (pin "25") (pinfunction "VCC_25") (pintype "power_in"))
      (node (ref "IC21") (pin "31") (pinfunction "VCC_31") (pintype "power_in"))
      (node (ref "IC21") (pin "35") (pinfunction "VCC_35") (pintype "power_in"))
      (node (ref "IC21") (pin "38") (pinfunction "VCC_38") (pintype "power_in"))
      (node (ref "IC21") (pin "42") (pinfunction "VCC_42") (pintype "power_in"))
      (node (ref "IC21") (pin "44") (pinfunction "BIASVCC_44") (pintype "input"))
      (node (ref "IC21") (pin "47") (pinfunction "VCC_47") (pintype "input"))
      (node (ref "IC21") (pin "7") (pinfunction "VCC_7") (pintype "power_in"))
      (node (ref "IC22") (pin "11") (pinfunction "LE_11") (pintype "input"))
      (node (ref "IC22") (pin "18") (pinfunction "VCC_18") (pintype "power_in"))
      (node (ref "IC22") (pin "25") (pinfunction "VCC_25") (pintype "power_in"))
      (node (ref "IC22") (pin "31") (pinfunction "VCC_31") (pintype "power_in"))
      (node (ref "IC22") (pin "35") (pinfunction "VCC_35") (pintype "power_in"))
      (node (ref "IC22") (pin "38") (pinfunction "VCC_38") (pintype "power_in"))
      (node (ref "IC22") (pin "42") (pinfunction "VCC_42") (pintype "power_in"))
      (node (ref "IC22") (pin "44") (pinfunction "BIASVCC_44") (pintype "input"))
      (node (ref "IC22") (pin "47") (pinfunction "VCC_47") (pintype "input"))
      (node (ref "IC22") (pin "7") (pinfunction "VCC_7") (pintype "power_in"))
      (node (ref "IC25") (pin "1") (pinfunction "~{1OEBY}_1") (pintype "input"))
      (node (ref "IC25") (pin "11") (pinfunction "LE_11") (pintype "input"))
      (node (ref "IC25") (pin "18") (pinfunction "VCC_18") (pintype "power_in"))
      (node (ref "IC25") (pin "25") (pinfunction "VCC_25") (pintype "power_in"))
      (node (ref "IC25") (pin "31") (pinfunction "VCC_31") (pintype "power_in"))
      (node (ref "IC25") (pin "35") (pinfunction "VCC_35") (pintype "power_in"))
      (node (ref "IC25") (pin "38") (pinfunction "VCC_38") (pintype "power_in"))
      (node (ref "IC25") (pin "42") (pinfunction "VCC_42") (pintype "power_in"))
      (node (ref "IC25") (pin "44") (pinfunction "BIASVCC_44") (pintype "input"))
      (node (ref "IC25") (pin "47") (pinfunction "VCC_47") (pintype "input"))
      (node (ref "IC25") (pin "7") (pinfunction "VCC_7") (pintype "power_in"))
      (node (ref "IC26") (pin "1") (pinfunction "~{1OEBY}_1") (pintype "input"))
      (node (ref "IC26") (pin "11") (pinfunction "LE_11") (pintype "input"))
      (node (ref "IC26") (pin "18") (pinfunction "VCC_18") (pintype "power_in"))
      (node (ref "IC26") (pin "25") (pinfunction "VCC_25") (pintype "power_in"))
      (node (ref "IC26") (pin "31") (pinfunction "VCC_31") (pintype "power_in"))
      (node (ref "IC26") (pin "35") (pinfunction "VCC_35") (pintype "power_in"))
      (node (ref "IC26") (pin "38") (pinfunction "VCC_38") (pintype "power_in"))
      (node (ref "IC26") (pin "42") (pinfunction "VCC_42") (pintype "power_in"))
      (node (ref "IC26") (pin "44") (pinfunction "BIASVCC_44") (pintype "input"))
      (node (ref "IC26") (pin "47") (pinfunction "VCC_47") (pintype "input"))
      (node (ref "IC26") (pin "7") (pinfunction "VCC_7") (pintype "power_in"))
      (node (ref "IC27") (pin "11") (pinfunction "LE_11") (pintype "input"))
      (node (ref "IC27") (pin "18") (pinfunction "VCC_18") (pintype "power_in"))
      (node (ref "IC27") (pin "25") (pinfunction "VCC_25") (pintype "power_in"))
      (node (ref "IC27") (pin "31") (pinfunction "VCC_31") (pintype "power_in"))
      (node (ref "IC27") (pin "35") (pinfunction "VCC_35") (pintype "power_in"))
      (node (ref "IC27") (pin "38") (pinfunction "VCC_38") (pintype "power_in"))
      (node (ref "IC27") (pin "42") (pinfunction "VCC_42") (pintype "power_in"))
      (node (ref "IC27") (pin "44") (pinfunction "BIASVCC_44") (pintype "input"))
      (node (ref "IC27") (pin "47") (pinfunction "VCC_47") (pintype "input"))
      (node (ref "IC27") (pin "7") (pinfunction "VCC_7") (pintype "power_in"))
      (node (ref "IC27") (pin "8") (pinfunction "2~{OEBY}_8") (pintype "input"))
      (node (ref "IC33") (pin "11") (pinfunction "LE_11") (pintype "input"))
      (node (ref "IC33") (pin "18") (pinfunction "VCC_18") (pintype "power_in"))
      (node (ref "IC33") (pin "25") (pinfunction "VCC_25") (pintype "power_in"))
      (node (ref "IC33") (pin "31") (pinfunction "VCC_31") (pintype "power_in"))
      (node (ref "IC33") (pin "35") (pinfunction "VCC_35") (pintype "power_in"))
      (node (ref "IC33") (pin "38") (pinfunction "VCC_38") (pintype "power_in"))
      (node (ref "IC33") (pin "41") (pinfunction "2OEAB_41") (pintype "input"))
      (node (ref "IC33") (pin "42") (pinfunction "VCC_42") (pintype "power_in"))
      (node (ref "IC33") (pin "44") (pinfunction "BIASVCC_44") (pintype "input"))
      (node (ref "IC33") (pin "47") (pinfunction "VCC_47") (pintype "input"))
      (node (ref "IC33") (pin "7") (pinfunction "VCC_7") (pintype "power_in"))
      (node (ref "IC33") (pin "8") (pinfunction "2~{OEBY}_8") (pintype "input"))
      (node (ref "IC35") (pin "1") (pinfunction "~{1OEBY}_1") (pintype "input"))
      (node (ref "IC35") (pin "11") (pinfunction "LE_11") (pintype "input"))
      (node (ref "IC35") (pin "18") (pinfunction "VCC_18") (pintype "power_in"))
      (node (ref "IC35") (pin "25") (pinfunction "VCC_25") (pintype "power_in"))
      (node (ref "IC35") (pin "31") (pinfunction "VCC_31") (pintype "power_in"))
      (node (ref "IC35") (pin "35") (pinfunction "VCC_35") (pintype "power_in"))
      (node (ref "IC35") (pin "38") (pinfunction "VCC_38") (pintype "power_in"))
      (node (ref "IC35") (pin "42") (pinfunction "VCC_42") (pintype "power_in"))
      (node (ref "IC35") (pin "44") (pinfunction "BIASVCC_44") (pintype "input"))
      (node (ref "IC35") (pin "47") (pinfunction "VCC_47") (pintype "input"))
      (node (ref "IC35") (pin "7") (pinfunction "VCC_7") (pintype "power_in"))
      (node (ref "IC35") (pin "8") (pinfunction "2~{OEBY}_8") (pintype "input"))
      (node (ref "IC42") (pin "1") (pinfunction "~{1OEBY}_1") (pintype "input"))
      (node (ref "IC42") (pin "11") (pinfunction "LE_11") (pintype "input"))
      (node (ref "IC42") (pin "18") (pinfunction "VCC_18") (pintype "power_in"))
      (node (ref "IC42") (pin "25") (pinfunction "VCC_25") (pintype "power_in"))
      (node (ref "IC42") (pin "31") (pinfunction "VCC_31") (pintype "power_in"))
      (node (ref "IC42") (pin "35") (pinfunction "VCC_35") (pintype "power_in"))
      (node (ref "IC42") (pin "38") (pinfunction "VCC_38") (pintype "power_in"))
      (node (ref "IC42") (pin "42") (pinfunction "VCC_42") (pintype "power_in"))
      (node (ref "IC42") (pin "44") (pinfunction "BIASVCC_44") (pintype "input"))
      (node (ref "IC42") (pin "47") (pinfunction "VCC_47") (pintype "input"))
      (node (ref "IC42") (pin "7") (pinfunction "VCC_7") (pintype "power_in"))
      (node (ref "IC42") (pin "8") (pinfunction "2~{OEBY}_8") (pintype "input"))
      (node (ref "IC5") (pin "1") (pinfunction "~{1OEBY}_1") (pintype "input"))
      (node (ref "IC5") (pin "11") (pinfunction "LE_11") (pintype "input"))
      (node (ref "IC5") (pin "18") (pinfunction "VCC_18") (pintype "power_in"))
      (node (ref "IC5") (pin "25") (pinfunction "VCC_25") (pintype "power_in"))
      (node (ref "IC5") (pin "31") (pinfunction "VCC_31") (pintype "power_in"))
      (node (ref "IC5") (pin "35") (pinfunction "VCC_35") (pintype "power_in"))
      (node (ref "IC5") (pin "38") (pinfunction "VCC_38") (pintype "power_in"))
      (node (ref "IC5") (pin "42") (pinfunction "VCC_42") (pintype "power_in"))
      (node (ref "IC5") (pin "44") (pinfunction "BIASVCC_44") (pintype "input"))
      (node (ref "IC5") (pin "47") (pinfunction "VCC_47") (pintype "input"))
      (node (ref "IC5") (pin "7") (pinfunction "VCC_7") (pintype "power_in"))
      (node (ref "IC5") (pin "8") (pinfunction "2~{OEBY}_8") (pintype "input"))
      (node (ref "P1") (pin "d12") (pinfunction "d12_d12") (pintype "bidirectional"))
      (node (ref "P1") (pin "d14") (pinfunction "d14_d14") (pintype "bidirectional"))
      (node (ref "P1") (pin "d16") (pinfunction "d16_d16") (pintype "bidirectional"))
      (node (ref "P1") (pin "d18") (pinfunction "d18_d18") (pintype "bidirectional"))
      (node (ref "P1") (pin "d20") (pinfunction "d20_d20") (pintype "bidirectional"))
      (node (ref "P1") (pin "d22") (pinfunction "d22_d22") (pintype "bidirectional"))
      (node (ref "P1") (pin "d24") (pinfunction "d24_d24") (pintype "bidirectional"))
      (node (ref "P1") (pin "d26") (pinfunction "d26_d26") (pintype "bidirectional"))
      (node (ref "P1") (pin "d28") (pinfunction "d28_d28") (pintype "bidirectional"))
      (node (ref "P1") (pin "d30") (pinfunction "d30_d30") (pintype "bidirectional"))
      (node (ref "R175") (pin "2") (pinfunction "2_2") (pintype "passive"))
      (node (ref "R203") (pin "2") (pinfunction "2_2") (pintype "passive"))
      (node (ref "R213") (pin "2") (pinfunction "2_2") (pintype "passive"))
      (node (ref "R216") (pin "2") (pinfunction "2_2") (pintype "passive"))
      (node (ref "R217") (pin "2") (pinfunction "2_2") (pintype "passive"))
      (node (ref "R223") (pin "2") (pinfunction "2_2") (pintype "passive"))
      (node (ref "R228") (pin "2") (pinfunction "2_2") (pintype "passive"))
      (node (ref "R230") (pin "2") (pinfunction "2_2") (pintype "passive"))
    )
    (net (code "276") (name "P5V_STDBY_VME") (class "Default")
      (node (ref "P1") (pin "b31") (pinfunction "b31_b31") (pintype "bidirectional"))
    )
    (net (code "277") (name "P5V_VME") (class "Default")
      (node (ref "P1") (pin "a32") (pinfunction "a32_a32") (pintype "bidirectional"))
      (node (ref "P1") (pin "b32") (pinfunction "b32_b32") (pintype "bidirectional"))
      (node (ref "P1") (pin "c32") (pinfunction "c32_c32") (pintype "bidirectional"))
      (node (ref "P3") (pin "b1") (pinfunction "b1_b1") (pintype "bidirectional"))
      (node (ref "P3") (pin "b13") (pinfunction "b13_b13") (pintype "bidirectional"))
      (node (ref "P3") (pin "b32") (pinfunction "b32_b32") (pintype "bidirectional"))
    )
    (net (code "278") (name "P12V_VME") (class "Default")
      (node (ref "P1") (pin "c31") (pinfunction "c31_c31") (pintype "bidirectional"))
    )
    (net (code "279") (name "unconnected-(IC5-1Y-Pad3)") (class "Default")
      (node (ref "IC5") (pin "3") (pinfunction "1Y_3") (pintype "output+no_connect"))
    )
    (net (code "280") (name "unconnected-(IC5-2Y-Pad6)") (class "Default")
      (node (ref "IC5") (pin "6") (pinfunction "2Y_6") (pintype "output+no_connect"))
    )
    (net (code "281") (name "unconnected-(IC15-1Y-Pad3)") (class "Default")
      (node (ref "IC15") (pin "3") (pinfunction "1Y_3") (pintype "output+no_connect"))
    )
    (net (code "282") (name "unconnected-(IC15-2Y-Pad6)") (class "Default")
      (node (ref "IC15") (pin "6") (pinfunction "2Y_6") (pintype "output+no_connect"))
    )
    (net (code "283") (name "unconnected-(IC25-1Y-Pad3)") (class "Default")
      (node (ref "IC25") (pin "3") (pinfunction "1Y_3") (pintype "output+no_connect"))
    )
    (net (code "284") (name "unconnected-(IC26-1Y-Pad3)") (class "Default")
      (node (ref "IC26") (pin "3") (pinfunction "1Y_3") (pintype "output+no_connect"))
    )
    (net (code "285") (name "unconnected-(IC27-2Y-Pad6)") (class "Default")
      (node (ref "IC27") (pin "6") (pinfunction "2Y_6") (pintype "output+no_connect"))
    )
    (net (code "286") (name "unconnected-(IC33-2Y-Pad6)") (class "Default")
      (node (ref "IC33") (pin "6") (pinfunction "2Y_6") (pintype "output+no_connect"))
    )
    (net (code "287") (name "unconnected-(IC35-1Y-Pad3)") (class "Default")
      (node (ref "IC35") (pin "3") (pinfunction "1Y_3") (pintype "output+no_connect"))
    )
    (net (code "288") (name "unconnected-(IC35-2Y-Pad6)") (class "Default")
      (node (ref "IC35") (pin "6") (pinfunction "2Y_6") (pintype "output+no_connect"))
    )
    (net (code "289") (name "unconnected-(IC42-1Y-Pad3)") (class "Default")
      (node (ref "IC42") (pin "3") (pinfunction "1Y_3") (pintype "output+no_connect"))
    )
    (net (code "290") (name "unconnected-(IC42-2Y-Pad6)") (class "Default")
      (node (ref "IC42") (pin "6") (pinfunction "2Y_6") (pintype "output+no_connect"))
    )
    (net (code "291") (name "unconnected-(P1-Padd1)") (class "Default")
      (node (ref "P1") (pin "d1") (pinfunction "d1_d1") (pintype "bidirectional+no_connect"))
    )
    (net (code "292") (name "unconnected-(P1-Padd3)") (class "Default")
      (node (ref "P1") (pin "d3") (pinfunction "d3_d3") (pintype "bidirectional+no_connect"))
    )
    (net (code "293") (name "unconnected-(P1-Padd4)") (class "Default")
      (node (ref "P1") (pin "d4") (pinfunction "d4_d4") (pintype "bidirectional+no_connect"))
    )
    (net (code "294") (name "unconnected-(P1-Padd5)") (class "Default")
      (node (ref "P1") (pin "d5") (pinfunction "d5_d5") (pintype "bidirectional+no_connect"))
    )
    (net (code "295") (name "unconnected-(P1-Padd6)") (class "Default")
      (node (ref "P1") (pin "d6") (pinfunction "d6_d6") (pintype "bidirectional+no_connect"))
    )
    (net (code "296") (name "unconnected-(P1-Padd7)") (class "Default")
      (node (ref "P1") (pin "d7") (pinfunction "d7_d7") (pintype "bidirectional+no_connect"))
    )
    (net (code "297") (name "unconnected-(P1-Padd8)") (class "Default")
      (node (ref "P1") (pin "d8") (pinfunction "d8_d8") (pintype "bidirectional+no_connect"))
    )
    (net (code "298") (name "unconnected-(P1-Padd19)") (class "Default")
      (node (ref "P1") (pin "d19") (pinfunction "d19_d19") (pintype "bidirectional+no_connect"))
    )
    (net (code "299") (name "unconnected-(P1-Padd21)") (class "Default")
      (node (ref "P1") (pin "d21") (pinfunction "d21_d21") (pintype "bidirectional+no_connect"))
    )
    (net (code "300") (name "unconnected-(P1-Padd23)") (class "Default")
      (node (ref "P1") (pin "d23") (pinfunction "d23_d23") (pintype "bidirectional+no_connect"))
    )
    (net (code "301") (name "unconnected-(P1-Padd25)") (class "Default")
      (node (ref "P1") (pin "d25") (pinfunction "d25_d25") (pintype "bidirectional+no_connect"))
    )
    (net (code "302") (name "unconnected-(P1-Padd27)") (class "Default")
      (node (ref "P1") (pin "d27") (pinfunction "d27_d27") (pintype "bidirectional+no_connect"))
    )
    (net (code "303") (name "unconnected-(P1-Padd29)") (class "Default")
      (node (ref "P1") (pin "d29") (pinfunction "d29_d29") (pintype "bidirectional+no_connect"))
    )
    (net (code "304") (name "unconnected-(P1-Padd32)") (class "Default")
      (node (ref "P1") (pin "d32") (pinfunction "d32_d32") (pintype "bidirectional+no_connect"))
    )
    (net (code "305") (name "unconnected-(P1-Padz11)") (class "Default")
      (node (ref "P1") (pin "z11") (pinfunction "z11_z11") (pintype "bidirectional+no_connect"))
    )
    (net (code "306") (name "unconnected-(P1-Padz13)") (class "Default")
      (node (ref "P1") (pin "z13") (pinfunction "z13_z13") (pintype "bidirectional+no_connect"))
    )
    (net (code "307") (name "unconnected-(P1-Padz15)") (class "Default")
      (node (ref "P1") (pin "z15") (pinfunction "z15_z15") (pintype "bidirectional+no_connect"))
    )
    (net (code "308") (name "unconnected-(P1-Padz17)") (class "Default")
      (node (ref "P1") (pin "z17") (pinfunction "z17_z17") (pintype "bidirectional+no_connect"))
    )
    (net (code "309") (name "unconnected-(P1-Padz19)") (class "Default")
      (node (ref "P1") (pin "z19") (pinfunction "z19_z19") (pintype "bidirectional+no_connect"))
    )
    (net (code "310") (name "unconnected-(P1-Padz21)") (class "Default")
      (node (ref "P1") (pin "z21") (pinfunction "z21_z21") (pintype "bidirectional+no_connect"))
    )
    (net (code "311") (name "unconnected-(P1-Padz23)") (class "Default")
      (node (ref "P1") (pin "z23") (pinfunction "z23_z23") (pintype "bidirectional+no_connect"))
    )
    (net (code "312") (name "unconnected-(P1-Padz25)") (class "Default")
      (node (ref "P1") (pin "z25") (pinfunction "z25_z25") (pintype "bidirectional+no_connect"))
    )
    (net (code "313") (name "unconnected-(P1-Padz27)") (class "Default")
      (node (ref "P1") (pin "z27") (pinfunction "z27_z27") (pintype "bidirectional+no_connect"))
    )
    (net (code "314") (name "unconnected-(P1-Padz29)") (class "Default")
      (node (ref "P1") (pin "z29") (pinfunction "z29_z29") (pintype "bidirectional+no_connect"))
    )
    (net (code "315") (name "unconnected-(P1-Padz31)") (class "Default")
      (node (ref "P1") (pin "z31") (pinfunction "z31_z31") (pintype "bidirectional+no_connect"))
    )
    (net (code "316") (name "unconnected-(P3-Padc1)") (class "Default")
      (node (ref "P3") (pin "c1") (pinfunction "c1_c1") (pintype "bidirectional"))
    )
    (net (code "317") (name "unconnected-(P3-Padc2)") (class "Default")
      (node (ref "P3") (pin "c2") (pinfunction "c2_c2") (pintype "bidirectional"))
    )
    (net (code "318") (name "unconnected-(P3-Padc3)") (class "Default")
      (node (ref "P3") (pin "c3") (pinfunction "c3_c3") (pintype "bidirectional"))
    )
    (net (code "319") (name "unconnected-(P3-Padc4)") (class "Default")
      (node (ref "P3") (pin "c4") (pinfunction "c4_c4") (pintype "bidirectional"))
    )
    (net (code "320") (name "unconnected-(P3-Padc5)") (class "Default")
      (node (ref "P3") (pin "c5") (pinfunction "c5_c5") (pintype "bidirectional"))
    )
    (net (code "321") (name "unconnected-(P3-Padc6)") (class "Default")
      (node (ref "P3") (pin "c6") (pinfunction "c6_c6") (pintype "bidirectional"))
    )
    (net (code "322") (name "unconnected-(P3-Padc7)") (class "Default")
      (node (ref "P3") (pin "c7") (pinfunction "c7_c7") (pintype "bidirectional"))
    )
    (net (code "323") (name "unconnected-(P3-Padc8)") (class "Default")
      (node (ref "P3") (pin "c8") (pinfunction "c8_c8") (pintype "bidirectional"))
    )
    (net (code "324") (name "unconnected-(P3-Padc9)") (class "Default")
      (node (ref "P3") (pin "c9") (pinfunction "c9_c9") (pintype "bidirectional"))
    )
    (net (code "325") (name "unconnected-(P3-Padc10)") (class "Default")
      (node (ref "P3") (pin "c10") (pinfunction "c10_c10") (pintype "bidirectional"))
    )
    (net (code "326") (name "unconnected-(P3-Padc11)") (class "Default")
      (node (ref "P3") (pin "c11") (pinfunction "c11_c11") (pintype "bidirectional"))
    )
    (net (code "327") (name "unconnected-(P3-Padc12)") (class "Default")
      (node (ref "P3") (pin "c12") (pinfunction "c12_c12") (pintype "bidirectional"))
    )
    (net (code "328") (name "unconnected-(P3-Padc13)") (class "Default")
      (node (ref "P3") (pin "c13") (pinfunction "c13_c13") (pintype "bidirectional"))
    )
    (net (code "329") (name "unconnected-(P3-Padc14)") (class "Default")
      (node (ref "P3") (pin "c14") (pinfunction "c14_c14") (pintype "bidirectional"))
    )
    (net (code "330") (name "unconnected-(P3-Padc15)") (class "Default")
      (node (ref "P3") (pin "c15") (pinfunction "c15_c15") (pintype "bidirectional"))
    )
    (net (code "331") (name "unconnected-(P3-Padc16)") (class "Default")
      (node (ref "P3") (pin "c16") (pinfunction "c16_c16") (pintype "bidirectional"))
    )
    (net (code "332") (name "unconnected-(P3-Padc17)") (class "Default")
      (node (ref "P3") (pin "c17") (pinfunction "c17_c17") (pintype "bidirectional"))
    )
    (net (code "333") (name "unconnected-(P3-Padc18)") (class "Default")
      (node (ref "P3") (pin "c18") (pinfunction "c18_c18") (pintype "bidirectional"))
    )
    (net (code "334") (name "unconnected-(P3-Padc19)") (class "Default")
      (node (ref "P3") (pin "c19") (pinfunction "c19_c19") (pintype "bidirectional"))
    )
    (net (code "335") (name "unconnected-(P3-Padc20)") (class "Default")
      (node (ref "P3") (pin "c20") (pinfunction "c20_c20") (pintype "bidirectional"))
    )
    (net (code "336") (name "unconnected-(P3-Padc21)") (class "Default")
      (node (ref "P3") (pin "c21") (pinfunction "c21_c21") (pintype "bidirectional"))
    )
    (net (code "337") (name "unconnected-(P3-Padc22)") (class "Default")
      (node (ref "P3") (pin "c22") (pinfunction "c22_c22") (pintype "bidirectional"))
    )
    (net (code "338") (name "unconnected-(P3-Padd32)") (class "Default")
      (node (ref "P3") (pin "d32") (pinfunction "d32_d32") (pintype "bidirectional+no_connect"))
    )
    (net (code "339") (name "unconnected-(P3-Padz1)") (class "Default")
      (node (ref "P3") (pin "z1") (pinfunction "z1_z1") (pintype "bidirectional+no_connect"))
    )
    (net (code "340") (name "unconnected-(P3-Padz3)") (class "Default")
      (node (ref "P3") (pin "z3") (pinfunction "z3_z3") (pintype "bidirectional+no_connect"))
    )
    (net (code "341") (name "unconnected-(P3-Padz5)") (class "Default")
      (node (ref "P3") (pin "z5") (pinfunction "z5_z5") (pintype "bidirectional+no_connect"))
    )
    (net (code "342") (name "unconnected-(P3-Padz7)") (class "Default")
      (node (ref "P3") (pin "z7") (pinfunction "z7_z7") (pintype "bidirectional+no_connect"))
    )
    (net (code "343") (name "unconnected-(P3-Padz9)") (class "Default")
      (node (ref "P3") (pin "z9") (pinfunction "z9_z9") (pintype "bidirectional+no_connect"))
    )
    (net (code "344") (name "unconnected-(P3-Padz11)") (class "Default")
      (node (ref "P3") (pin "z11") (pinfunction "z11_z11") (pintype "bidirectional+no_connect"))
    )
    (net (code "345") (name "unconnected-(P3-Padz13)") (class "Default")
      (node (ref "P3") (pin "z13") (pinfunction "z13_z13") (pintype "bidirectional+no_connect"))
    )
    (net (code "346") (name "unconnected-(P3-Padz15)") (class "Default")
      (node (ref "P3") (pin "z15") (pinfunction "z15_z15") (pintype "bidirectional+no_connect"))
    )
    (net (code "347") (name "unconnected-(P3-Padz17)") (class "Default")
      (node (ref "P3") (pin "z17") (pinfunction "z17_z17") (pintype "bidirectional+no_connect"))
    )
    (net (code "348") (name "unconnected-(P3-Padz19)") (class "Default")
      (node (ref "P3") (pin "z19") (pinfunction "z19_z19") (pintype "bidirectional+no_connect"))
    )
    (net (code "349") (name "unconnected-(P3-Padz21)") (class "Default")
      (node (ref "P3") (pin "z21") (pinfunction "z21_z21") (pintype "bidirectional+no_connect"))
    )
    (net (code "350") (name "unconnected-(P3-Padz23)") (class "Default")
      (node (ref "P3") (pin "z23") (pinfunction "z23_z23") (pintype "bidirectional+no_connect"))
    )
    (net (code "351") (name "unconnected-(P3-Padz25)") (class "Default")
      (node (ref "P3") (pin "z25") (pinfunction "z25_z25") (pintype "bidirectional+no_connect"))
    )
    (net (code "352") (name "unconnected-(P3-Padz27)") (class "Default")
      (node (ref "P3") (pin "z27") (pinfunction "z27_z27") (pintype "bidirectional+no_connect"))
    )
    (net (code "353") (name "unconnected-(P3-Padz29)") (class "Default")
      (node (ref "P3") (pin "z29") (pinfunction "z29_z29") (pintype "bidirectional+no_connect"))
    )
    (net (code "354") (name "unconnected-(P3-Padz31)") (class "Default")
      (node (ref "P3") (pin "z31") (pinfunction "z31_z31") (pintype "bidirectional+no_connect"))
    )
  )
)
